# Proto2.net
KiCad netlist of a schematic drawn in EAGLE
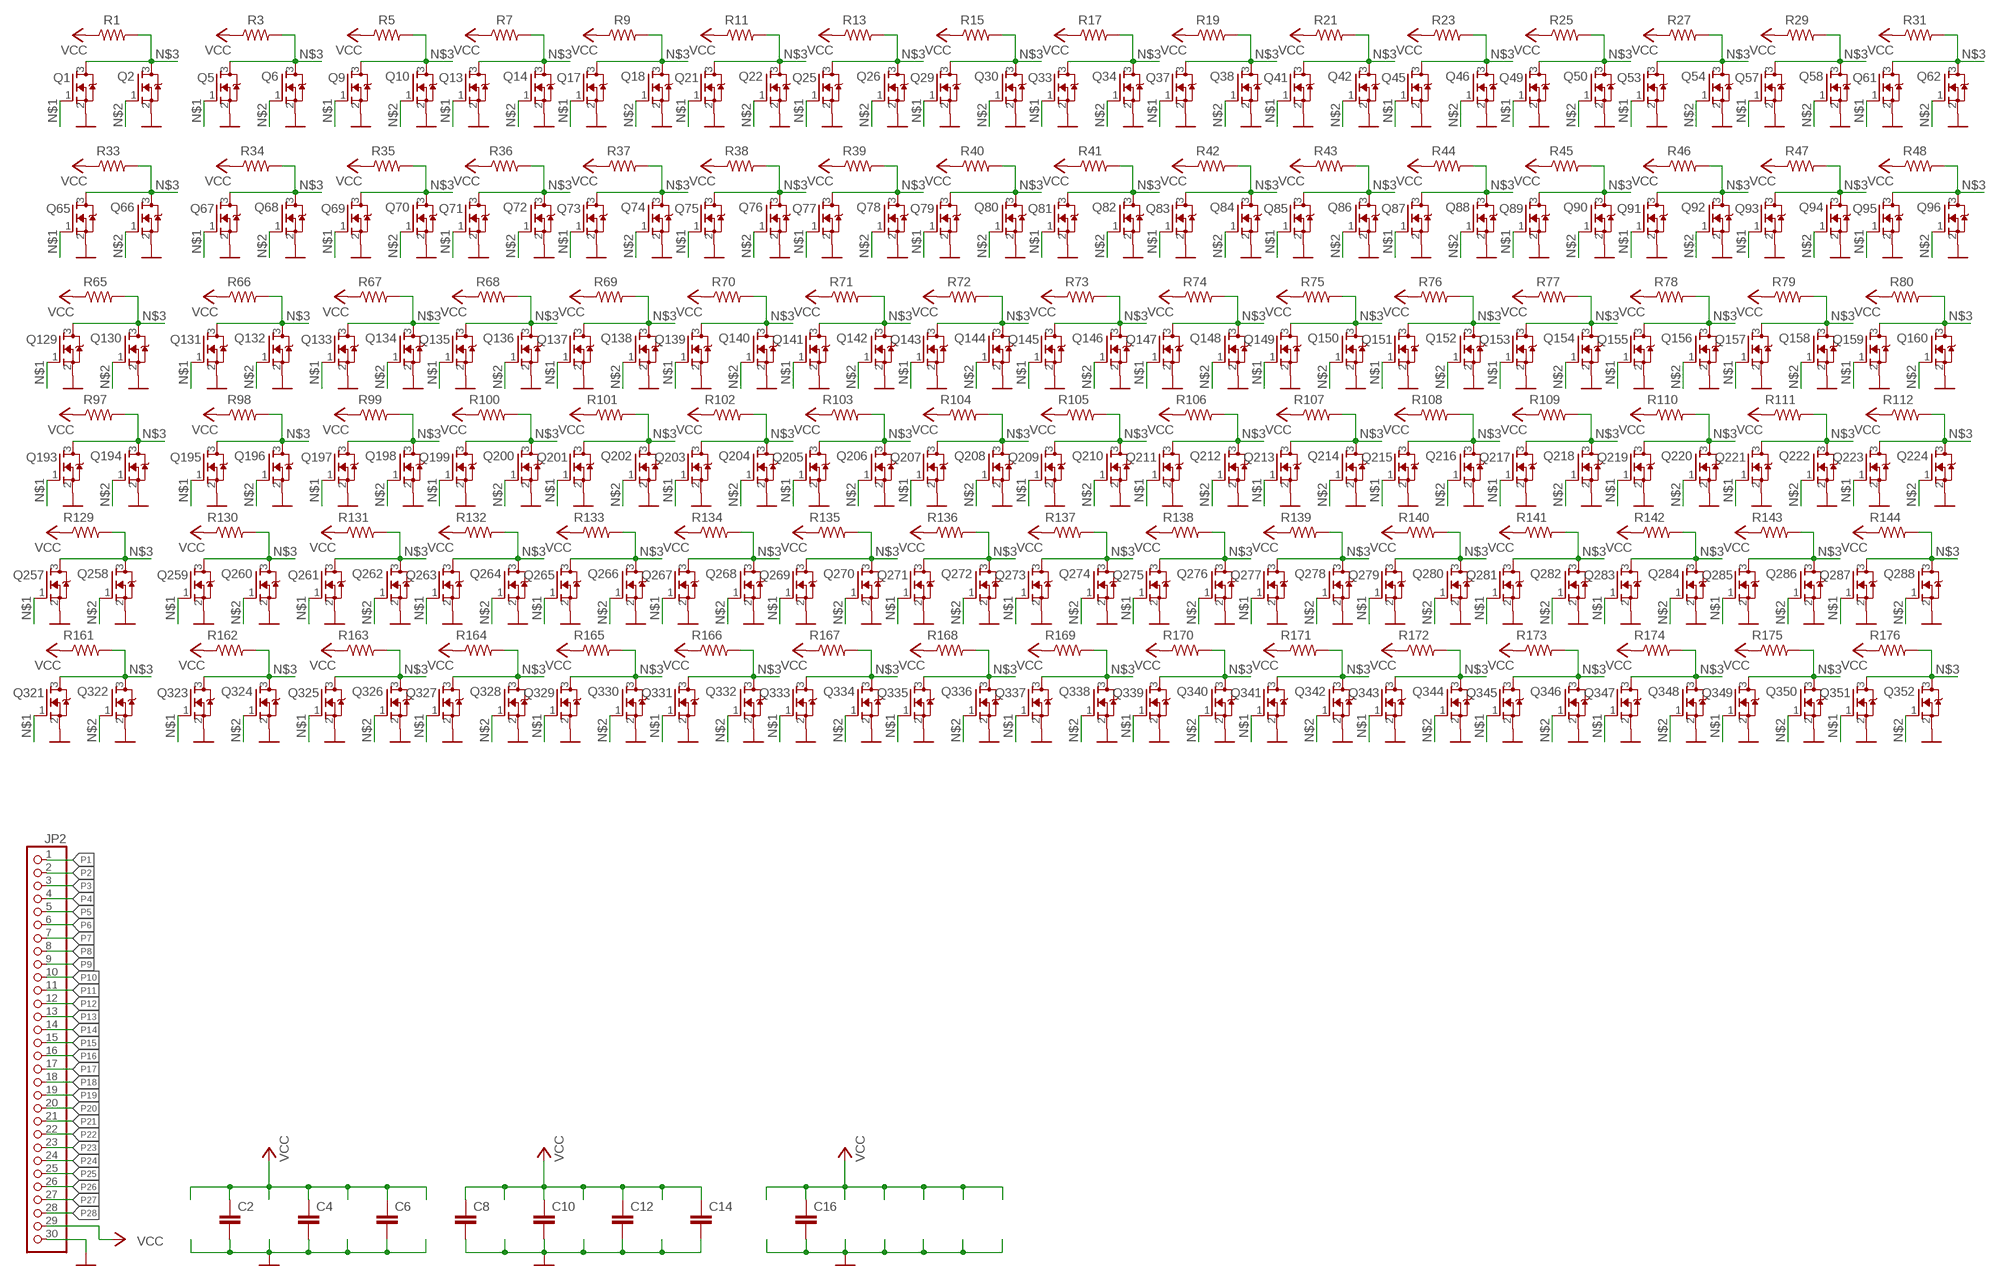
[diagram p0: schematic, sheet 1]

(export (version "E")
  (design (tool "Eeschema 10.0.6"))
  (components
    (comp (ref "C2")
      (value "C-EUC0805K")
      (footprint "eagle-import:C0805K")
      (libsource (lib "eagle-import") (part "C-EUC0805K"))
    )
    (comp (ref "C4")
      (value "C-EUC0805K")
      (footprint "eagle-import:C0805K")
      (libsource (lib "eagle-import") (part "C-EUC0805K"))
    )
    (comp (ref "C6")
      (value "C-EUC0805K")
      (footprint "eagle-import:C0805K")
      (libsource (lib "eagle-import") (part "C-EUC0805K"))
    )
    (comp (ref "C8")
      (value "C-EUC0805K")
      (footprint "eagle-import:C0805K")
      (libsource (lib "eagle-import") (part "C-EUC0805K"))
    )
    (comp (ref "C10")
      (value "C-EUC0805K")
      (footprint "eagle-import:C0805K")
      (libsource (lib "eagle-import") (part "C-EUC0805K"))
    )
    (comp (ref "C12")
      (value "C-EUC0805K")
      (footprint "eagle-import:C0805K")
      (libsource (lib "eagle-import") (part "C-EUC0805K"))
    )
    (comp (ref "C14")
      (value "C-EUC0805K")
      (footprint "eagle-import:C0805K")
      (libsource (lib "eagle-import") (part "C-EUC0805K"))
    )
    (comp (ref "C16")
      (value "C-EUC0805K")
      (footprint "eagle-import:C0805K")
      (libsource (lib "eagle-import") (part "C-EUC0805K"))
    )
    (comp (ref "JP2")
      (value "PINHD-1X30")
      (footprint "eagle-import:1X30")
      (libsource (lib "eagle-import") (part "PINHD-1X30"))
    )
    (comp (ref "Q1")
      (value "310mA/60V/1.6Ω")
      (footprint "eagle-import:SOT23")
      (libsource (lib "eagle-import") (part "NMOSREFLOW"))
    )
    (comp (ref "Q2")
      (value "310mA/60V/1.6Ω")
      (footprint "eagle-import:SOT23")
      (libsource (lib "eagle-import") (part "NMOSREFLOW"))
    )
    (comp (ref "Q5")
      (value "310mA/60V/1.6Ω")
      (footprint "eagle-import:SOT23")
      (libsource (lib "eagle-import") (part "NMOSREFLOW"))
    )
    (comp (ref "Q6")
      (value "310mA/60V/1.6Ω")
      (footprint "eagle-import:SOT23")
      (libsource (lib "eagle-import") (part "NMOSREFLOW"))
    )
    (comp (ref "Q9")
      (value "310mA/60V/1.6Ω")
      (footprint "eagle-import:SOT23")
      (libsource (lib "eagle-import") (part "NMOSREFLOW"))
    )
    (comp (ref "Q10")
      (value "310mA/60V/1.6Ω")
      (footprint "eagle-import:SOT23")
      (libsource (lib "eagle-import") (part "NMOSREFLOW"))
    )
    (comp (ref "Q13")
      (value "310mA/60V/1.6Ω")
      (footprint "eagle-import:SOT23")
      (libsource (lib "eagle-import") (part "NMOSREFLOW"))
    )
    (comp (ref "Q14")
      (value "310mA/60V/1.6Ω")
      (footprint "eagle-import:SOT23")
      (libsource (lib "eagle-import") (part "NMOSREFLOW"))
    )
    (comp (ref "Q17")
      (value "310mA/60V/1.6Ω")
      (footprint "eagle-import:SOT23")
      (libsource (lib "eagle-import") (part "NMOSREFLOW"))
    )
    (comp (ref "Q18")
      (value "310mA/60V/1.6Ω")
      (footprint "eagle-import:SOT23")
      (libsource (lib "eagle-import") (part "NMOSREFLOW"))
    )
    (comp (ref "Q21")
      (value "310mA/60V/1.6Ω")
      (footprint "eagle-import:SOT23")
      (libsource (lib "eagle-import") (part "NMOSREFLOW"))
    )
    (comp (ref "Q22")
      (value "310mA/60V/1.6Ω")
      (footprint "eagle-import:SOT23")
      (libsource (lib "eagle-import") (part "NMOSREFLOW"))
    )
    (comp (ref "Q25")
      (value "310mA/60V/1.6Ω")
      (footprint "eagle-import:SOT23")
      (libsource (lib "eagle-import") (part "NMOSREFLOW"))
    )
    (comp (ref "Q26")
      (value "310mA/60V/1.6Ω")
      (footprint "eagle-import:SOT23")
      (libsource (lib "eagle-import") (part "NMOSREFLOW"))
    )
    (comp (ref "Q29")
      (value "310mA/60V/1.6Ω")
      (footprint "eagle-import:SOT23")
      (libsource (lib "eagle-import") (part "NMOSREFLOW"))
    )
    (comp (ref "Q30")
      (value "310mA/60V/1.6Ω")
      (footprint "eagle-import:SOT23")
      (libsource (lib "eagle-import") (part "NMOSREFLOW"))
    )
    (comp (ref "Q33")
      (value "310mA/60V/1.6Ω")
      (footprint "eagle-import:SOT23")
      (libsource (lib "eagle-import") (part "NMOSREFLOW"))
    )
    (comp (ref "Q34")
      (value "310mA/60V/1.6Ω")
      (footprint "eagle-import:SOT23")
      (libsource (lib "eagle-import") (part "NMOSREFLOW"))
    )
    (comp (ref "Q37")
      (value "310mA/60V/1.6Ω")
      (footprint "eagle-import:SOT23")
      (libsource (lib "eagle-import") (part "NMOSREFLOW"))
    )
    (comp (ref "Q38")
      (value "310mA/60V/1.6Ω")
      (footprint "eagle-import:SOT23")
      (libsource (lib "eagle-import") (part "NMOSREFLOW"))
    )
    (comp (ref "Q41")
      (value "310mA/60V/1.6Ω")
      (footprint "eagle-import:SOT23")
      (libsource (lib "eagle-import") (part "NMOSREFLOW"))
    )
    (comp (ref "Q42")
      (value "310mA/60V/1.6Ω")
      (footprint "eagle-import:SOT23")
      (libsource (lib "eagle-import") (part "NMOSREFLOW"))
    )
    (comp (ref "Q45")
      (value "310mA/60V/1.6Ω")
      (footprint "eagle-import:SOT23")
      (libsource (lib "eagle-import") (part "NMOSREFLOW"))
    )
    (comp (ref "Q46")
      (value "310mA/60V/1.6Ω")
      (footprint "eagle-import:SOT23")
      (libsource (lib "eagle-import") (part "NMOSREFLOW"))
    )
    (comp (ref "Q49")
      (value "310mA/60V/1.6Ω")
      (footprint "eagle-import:SOT23")
      (libsource (lib "eagle-import") (part "NMOSREFLOW"))
    )
    (comp (ref "Q50")
      (value "310mA/60V/1.6Ω")
      (footprint "eagle-import:SOT23")
      (libsource (lib "eagle-import") (part "NMOSREFLOW"))
    )
    (comp (ref "Q53")
      (value "310mA/60V/1.6Ω")
      (footprint "eagle-import:SOT23")
      (libsource (lib "eagle-import") (part "NMOSREFLOW"))
    )
    (comp (ref "Q54")
      (value "310mA/60V/1.6Ω")
      (footprint "eagle-import:SOT23")
      (libsource (lib "eagle-import") (part "NMOSREFLOW"))
    )
    (comp (ref "Q57")
      (value "310mA/60V/1.6Ω")
      (footprint "eagle-import:SOT23")
      (libsource (lib "eagle-import") (part "NMOSREFLOW"))
    )
    (comp (ref "Q58")
      (value "310mA/60V/1.6Ω")
      (footprint "eagle-import:SOT23")
      (libsource (lib "eagle-import") (part "NMOSREFLOW"))
    )
    (comp (ref "Q61")
      (value "310mA/60V/1.6Ω")
      (footprint "eagle-import:SOT23")
      (libsource (lib "eagle-import") (part "NMOSREFLOW"))
    )
    (comp (ref "Q62")
      (value "310mA/60V/1.6Ω")
      (footprint "eagle-import:SOT23")
      (libsource (lib "eagle-import") (part "NMOSREFLOW"))
    )
    (comp (ref "Q65")
      (value "310mA/60V/1.6Ω")
      (footprint "eagle-import:SOT23")
      (libsource (lib "eagle-import") (part "NMOSREFLOW"))
    )
    (comp (ref "Q66")
      (value "310mA/60V/1.6Ω")
      (footprint "eagle-import:SOT23")
      (libsource (lib "eagle-import") (part "NMOSREFLOW"))
    )
    (comp (ref "Q67")
      (value "310mA/60V/1.6Ω")
      (footprint "eagle-import:SOT23")
      (libsource (lib "eagle-import") (part "NMOSREFLOW"))
    )
    (comp (ref "Q68")
      (value "310mA/60V/1.6Ω")
      (footprint "eagle-import:SOT23")
      (libsource (lib "eagle-import") (part "NMOSREFLOW"))
    )
    (comp (ref "Q69")
      (value "310mA/60V/1.6Ω")
      (footprint "eagle-import:SOT23")
      (libsource (lib "eagle-import") (part "NMOSREFLOW"))
    )
    (comp (ref "Q70")
      (value "310mA/60V/1.6Ω")
      (footprint "eagle-import:SOT23")
      (libsource (lib "eagle-import") (part "NMOSREFLOW"))
    )
    (comp (ref "Q71")
      (value "310mA/60V/1.6Ω")
      (footprint "eagle-import:SOT23")
      (libsource (lib "eagle-import") (part "NMOSREFLOW"))
    )
    (comp (ref "Q72")
      (value "310mA/60V/1.6Ω")
      (footprint "eagle-import:SOT23")
      (libsource (lib "eagle-import") (part "NMOSREFLOW"))
    )
    (comp (ref "Q73")
      (value "310mA/60V/1.6Ω")
      (footprint "eagle-import:SOT23")
      (libsource (lib "eagle-import") (part "NMOSREFLOW"))
    )
    (comp (ref "Q74")
      (value "310mA/60V/1.6Ω")
      (footprint "eagle-import:SOT23")
      (libsource (lib "eagle-import") (part "NMOSREFLOW"))
    )
    (comp (ref "Q75")
      (value "310mA/60V/1.6Ω")
      (footprint "eagle-import:SOT23")
      (libsource (lib "eagle-import") (part "NMOSREFLOW"))
    )
    (comp (ref "Q76")
      (value "310mA/60V/1.6Ω")
      (footprint "eagle-import:SOT23")
      (libsource (lib "eagle-import") (part "NMOSREFLOW"))
    )
    (comp (ref "Q77")
      (value "310mA/60V/1.6Ω")
      (footprint "eagle-import:SOT23")
      (libsource (lib "eagle-import") (part "NMOSREFLOW"))
    )
    (comp (ref "Q78")
      (value "310mA/60V/1.6Ω")
      (footprint "eagle-import:SOT23")
      (libsource (lib "eagle-import") (part "NMOSREFLOW"))
    )
    (comp (ref "Q79")
      (value "310mA/60V/1.6Ω")
      (footprint "eagle-import:SOT23")
      (libsource (lib "eagle-import") (part "NMOSREFLOW"))
    )
    (comp (ref "Q80")
      (value "310mA/60V/1.6Ω")
      (footprint "eagle-import:SOT23")
      (libsource (lib "eagle-import") (part "NMOSREFLOW"))
    )
    (comp (ref "Q81")
      (value "310mA/60V/1.6Ω")
      (footprint "eagle-import:SOT23")
      (libsource (lib "eagle-import") (part "NMOSREFLOW"))
    )
    (comp (ref "Q82")
      (value "310mA/60V/1.6Ω")
      (footprint "eagle-import:SOT23")
      (libsource (lib "eagle-import") (part "NMOSREFLOW"))
    )
    (comp (ref "Q83")
      (value "310mA/60V/1.6Ω")
      (footprint "eagle-import:SOT23")
      (libsource (lib "eagle-import") (part "NMOSREFLOW"))
    )
    (comp (ref "Q84")
      (value "310mA/60V/1.6Ω")
      (footprint "eagle-import:SOT23")
      (libsource (lib "eagle-import") (part "NMOSREFLOW"))
    )
    (comp (ref "Q85")
      (value "310mA/60V/1.6Ω")
      (footprint "eagle-import:SOT23")
      (libsource (lib "eagle-import") (part "NMOSREFLOW"))
    )
    (comp (ref "Q86")
      (value "310mA/60V/1.6Ω")
      (footprint "eagle-import:SOT23")
      (libsource (lib "eagle-import") (part "NMOSREFLOW"))
    )
    (comp (ref "Q87")
      (value "310mA/60V/1.6Ω")
      (footprint "eagle-import:SOT23")
      (libsource (lib "eagle-import") (part "NMOSREFLOW"))
    )
    (comp (ref "Q88")
      (value "310mA/60V/1.6Ω")
      (footprint "eagle-import:SOT23")
      (libsource (lib "eagle-import") (part "NMOSREFLOW"))
    )
    (comp (ref "Q89")
      (value "310mA/60V/1.6Ω")
      (footprint "eagle-import:SOT23")
      (libsource (lib "eagle-import") (part "NMOSREFLOW"))
    )
    (comp (ref "Q90")
      (value "310mA/60V/1.6Ω")
      (footprint "eagle-import:SOT23")
      (libsource (lib "eagle-import") (part "NMOSREFLOW"))
    )
    (comp (ref "Q91")
      (value "310mA/60V/1.6Ω")
      (footprint "eagle-import:SOT23")
      (libsource (lib "eagle-import") (part "NMOSREFLOW"))
    )
    (comp (ref "Q92")
      (value "310mA/60V/1.6Ω")
      (footprint "eagle-import:SOT23")
      (libsource (lib "eagle-import") (part "NMOSREFLOW"))
    )
    (comp (ref "Q93")
      (value "310mA/60V/1.6Ω")
      (footprint "eagle-import:SOT23")
      (libsource (lib "eagle-import") (part "NMOSREFLOW"))
    )
    (comp (ref "Q94")
      (value "310mA/60V/1.6Ω")
      (footprint "eagle-import:SOT23")
      (libsource (lib "eagle-import") (part "NMOSREFLOW"))
    )
    (comp (ref "Q95")
      (value "310mA/60V/1.6Ω")
      (footprint "eagle-import:SOT23")
      (libsource (lib "eagle-import") (part "NMOSREFLOW"))
    )
    (comp (ref "Q96")
      (value "310mA/60V/1.6Ω")
      (footprint "eagle-import:SOT23")
      (libsource (lib "eagle-import") (part "NMOSREFLOW"))
    )
    (comp (ref "Q129")
      (value "310mA/60V/1.6Ω")
      (footprint "eagle-import:SOT23")
      (libsource (lib "eagle-import") (part "NMOSREFLOW"))
    )
    (comp (ref "Q130")
      (value "310mA/60V/1.6Ω")
      (footprint "eagle-import:SOT23")
      (libsource (lib "eagle-import") (part "NMOSREFLOW"))
    )
    (comp (ref "Q131")
      (value "310mA/60V/1.6Ω")
      (footprint "eagle-import:SOT23")
      (libsource (lib "eagle-import") (part "NMOSREFLOW"))
    )
    (comp (ref "Q132")
      (value "310mA/60V/1.6Ω")
      (footprint "eagle-import:SOT23")
      (libsource (lib "eagle-import") (part "NMOSREFLOW"))
    )
    (comp (ref "Q133")
      (value "310mA/60V/1.6Ω")
      (footprint "eagle-import:SOT23")
      (libsource (lib "eagle-import") (part "NMOSREFLOW"))
    )
    (comp (ref "Q134")
      (value "310mA/60V/1.6Ω")
      (footprint "eagle-import:SOT23")
      (libsource (lib "eagle-import") (part "NMOSREFLOW"))
    )
    (comp (ref "Q135")
      (value "310mA/60V/1.6Ω")
      (footprint "eagle-import:SOT23")
      (libsource (lib "eagle-import") (part "NMOSREFLOW"))
    )
    (comp (ref "Q136")
      (value "310mA/60V/1.6Ω")
      (footprint "eagle-import:SOT23")
      (libsource (lib "eagle-import") (part "NMOSREFLOW"))
    )
    (comp (ref "Q137")
      (value "310mA/60V/1.6Ω")
      (footprint "eagle-import:SOT23")
      (libsource (lib "eagle-import") (part "NMOSREFLOW"))
    )
    (comp (ref "Q138")
      (value "310mA/60V/1.6Ω")
      (footprint "eagle-import:SOT23")
      (libsource (lib "eagle-import") (part "NMOSREFLOW"))
    )
    (comp (ref "Q139")
      (value "310mA/60V/1.6Ω")
      (footprint "eagle-import:SOT23")
      (libsource (lib "eagle-import") (part "NMOSREFLOW"))
    )
    (comp (ref "Q140")
      (value "310mA/60V/1.6Ω")
      (footprint "eagle-import:SOT23")
      (libsource (lib "eagle-import") (part "NMOSREFLOW"))
    )
    (comp (ref "Q141")
      (value "310mA/60V/1.6Ω")
      (footprint "eagle-import:SOT23")
      (libsource (lib "eagle-import") (part "NMOSREFLOW"))
    )
    (comp (ref "Q142")
      (value "310mA/60V/1.6Ω")
      (footprint "eagle-import:SOT23")
      (libsource (lib "eagle-import") (part "NMOSREFLOW"))
    )
    (comp (ref "Q143")
      (value "310mA/60V/1.6Ω")
      (footprint "eagle-import:SOT23")
      (libsource (lib "eagle-import") (part "NMOSREFLOW"))
    )
    (comp (ref "Q144")
      (value "310mA/60V/1.6Ω")
      (footprint "eagle-import:SOT23")
      (libsource (lib "eagle-import") (part "NMOSREFLOW"))
    )
    (comp (ref "Q145")
      (value "310mA/60V/1.6Ω")
      (footprint "eagle-import:SOT23")
      (libsource (lib "eagle-import") (part "NMOSREFLOW"))
    )
    (comp (ref "Q146")
      (value "310mA/60V/1.6Ω")
      (footprint "eagle-import:SOT23")
      (libsource (lib "eagle-import") (part "NMOSREFLOW"))
    )
    (comp (ref "Q147")
      (value "310mA/60V/1.6Ω")
      (footprint "eagle-import:SOT23")
      (libsource (lib "eagle-import") (part "NMOSREFLOW"))
    )
    (comp (ref "Q148")
      (value "310mA/60V/1.6Ω")
      (footprint "eagle-import:SOT23")
      (libsource (lib "eagle-import") (part "NMOSREFLOW"))
    )
    (comp (ref "Q149")
      (value "310mA/60V/1.6Ω")
      (footprint "eagle-import:SOT23")
      (libsource (lib "eagle-import") (part "NMOSREFLOW"))
    )
    (comp (ref "Q150")
      (value "310mA/60V/1.6Ω")
      (footprint "eagle-import:SOT23")
      (libsource (lib "eagle-import") (part "NMOSREFLOW"))
    )
    (comp (ref "Q151")
      (value "310mA/60V/1.6Ω")
      (footprint "eagle-import:SOT23")
      (libsource (lib "eagle-import") (part "NMOSREFLOW"))
    )
    (comp (ref "Q152")
      (value "310mA/60V/1.6Ω")
      (footprint "eagle-import:SOT23")
      (libsource (lib "eagle-import") (part "NMOSREFLOW"))
    )
    (comp (ref "Q153")
      (value "310mA/60V/1.6Ω")
      (footprint "eagle-import:SOT23")
      (libsource (lib "eagle-import") (part "NMOSREFLOW"))
    )
    (comp (ref "Q154")
      (value "310mA/60V/1.6Ω")
      (footprint "eagle-import:SOT23")
      (libsource (lib "eagle-import") (part "NMOSREFLOW"))
    )
    (comp (ref "Q155")
      (value "310mA/60V/1.6Ω")
      (footprint "eagle-import:SOT23")
      (libsource (lib "eagle-import") (part "NMOSREFLOW"))
    )
    (comp (ref "Q156")
      (value "310mA/60V/1.6Ω")
      (footprint "eagle-import:SOT23")
      (libsource (lib "eagle-import") (part "NMOSREFLOW"))
    )
    (comp (ref "Q157")
      (value "310mA/60V/1.6Ω")
      (footprint "eagle-import:SOT23")
      (libsource (lib "eagle-import") (part "NMOSREFLOW"))
    )
    (comp (ref "Q158")
      (value "310mA/60V/1.6Ω")
      (footprint "eagle-import:SOT23")
      (libsource (lib "eagle-import") (part "NMOSREFLOW"))
    )
    (comp (ref "Q159")
      (value "310mA/60V/1.6Ω")
      (footprint "eagle-import:SOT23")
      (libsource (lib "eagle-import") (part "NMOSREFLOW"))
    )
    (comp (ref "Q160")
      (value "310mA/60V/1.6Ω")
      (footprint "eagle-import:SOT23")
      (libsource (lib "eagle-import") (part "NMOSREFLOW"))
    )
    (comp (ref "Q193")
      (value "310mA/60V/1.6Ω")
      (footprint "eagle-import:SOT23")
      (libsource (lib "eagle-import") (part "NMOSREFLOW"))
    )
    (comp (ref "Q194")
      (value "310mA/60V/1.6Ω")
      (footprint "eagle-import:SOT23")
      (libsource (lib "eagle-import") (part "NMOSREFLOW"))
    )
    (comp (ref "Q195")
      (value "310mA/60V/1.6Ω")
      (footprint "eagle-import:SOT23")
      (libsource (lib "eagle-import") (part "NMOSREFLOW"))
    )
    (comp (ref "Q196")
      (value "310mA/60V/1.6Ω")
      (footprint "eagle-import:SOT23")
      (libsource (lib "eagle-import") (part "NMOSREFLOW"))
    )
    (comp (ref "Q197")
      (value "310mA/60V/1.6Ω")
      (footprint "eagle-import:SOT23")
      (libsource (lib "eagle-import") (part "NMOSREFLOW"))
    )
    (comp (ref "Q198")
      (value "310mA/60V/1.6Ω")
      (footprint "eagle-import:SOT23")
      (libsource (lib "eagle-import") (part "NMOSREFLOW"))
    )
    (comp (ref "Q199")
      (value "310mA/60V/1.6Ω")
      (footprint "eagle-import:SOT23")
      (libsource (lib "eagle-import") (part "NMOSREFLOW"))
    )
    (comp (ref "Q200")
      (value "310mA/60V/1.6Ω")
      (footprint "eagle-import:SOT23")
      (libsource (lib "eagle-import") (part "NMOSREFLOW"))
    )
    (comp (ref "Q201")
      (value "310mA/60V/1.6Ω")
      (footprint "eagle-import:SOT23")
      (libsource (lib "eagle-import") (part "NMOSREFLOW"))
    )
    (comp (ref "Q202")
      (value "310mA/60V/1.6Ω")
      (footprint "eagle-import:SOT23")
      (libsource (lib "eagle-import") (part "NMOSREFLOW"))
    )
    (comp (ref "Q203")
      (value "310mA/60V/1.6Ω")
      (footprint "eagle-import:SOT23")
      (libsource (lib "eagle-import") (part "NMOSREFLOW"))
    )
    (comp (ref "Q204")
      (value "310mA/60V/1.6Ω")
      (footprint "eagle-import:SOT23")
      (libsource (lib "eagle-import") (part "NMOSREFLOW"))
    )
    (comp (ref "Q205")
      (value "310mA/60V/1.6Ω")
      (footprint "eagle-import:SOT23")
      (libsource (lib "eagle-import") (part "NMOSREFLOW"))
    )
    (comp (ref "Q206")
      (value "310mA/60V/1.6Ω")
      (footprint "eagle-import:SOT23")
      (libsource (lib "eagle-import") (part "NMOSREFLOW"))
    )
    (comp (ref "Q207")
      (value "310mA/60V/1.6Ω")
      (footprint "eagle-import:SOT23")
      (libsource (lib "eagle-import") (part "NMOSREFLOW"))
    )
    (comp (ref "Q208")
      (value "310mA/60V/1.6Ω")
      (footprint "eagle-import:SOT23")
      (libsource (lib "eagle-import") (part "NMOSREFLOW"))
    )
    (comp (ref "Q209")
      (value "310mA/60V/1.6Ω")
      (footprint "eagle-import:SOT23")
      (libsource (lib "eagle-import") (part "NMOSREFLOW"))
    )
    (comp (ref "Q210")
      (value "310mA/60V/1.6Ω")
      (footprint "eagle-import:SOT23")
      (libsource (lib "eagle-import") (part "NMOSREFLOW"))
    )
    (comp (ref "Q211")
      (value "310mA/60V/1.6Ω")
      (footprint "eagle-import:SOT23")
      (libsource (lib "eagle-import") (part "NMOSREFLOW"))
    )
    (comp (ref "Q212")
      (value "310mA/60V/1.6Ω")
      (footprint "eagle-import:SOT23")
      (libsource (lib "eagle-import") (part "NMOSREFLOW"))
    )
    (comp (ref "Q213")
      (value "310mA/60V/1.6Ω")
      (footprint "eagle-import:SOT23")
      (libsource (lib "eagle-import") (part "NMOSREFLOW"))
    )
    (comp (ref "Q214")
      (value "310mA/60V/1.6Ω")
      (footprint "eagle-import:SOT23")
      (libsource (lib "eagle-import") (part "NMOSREFLOW"))
    )
    (comp (ref "Q215")
      (value "310mA/60V/1.6Ω")
      (footprint "eagle-import:SOT23")
      (libsource (lib "eagle-import") (part "NMOSREFLOW"))
    )
    (comp (ref "Q216")
      (value "310mA/60V/1.6Ω")
      (footprint "eagle-import:SOT23")
      (libsource (lib "eagle-import") (part "NMOSREFLOW"))
    )
    (comp (ref "Q217")
      (value "310mA/60V/1.6Ω")
      (footprint "eagle-import:SOT23")
      (libsource (lib "eagle-import") (part "NMOSREFLOW"))
    )
    (comp (ref "Q218")
      (value "310mA/60V/1.6Ω")
      (footprint "eagle-import:SOT23")
      (libsource (lib "eagle-import") (part "NMOSREFLOW"))
    )
    (comp (ref "Q219")
      (value "310mA/60V/1.6Ω")
      (footprint "eagle-import:SOT23")
      (libsource (lib "eagle-import") (part "NMOSREFLOW"))
    )
    (comp (ref "Q220")
      (value "310mA/60V/1.6Ω")
      (footprint "eagle-import:SOT23")
      (libsource (lib "eagle-import") (part "NMOSREFLOW"))
    )
    (comp (ref "Q221")
      (value "310mA/60V/1.6Ω")
      (footprint "eagle-import:SOT23")
      (libsource (lib "eagle-import") (part "NMOSREFLOW"))
    )
    (comp (ref "Q222")
      (value "310mA/60V/1.6Ω")
      (footprint "eagle-import:SOT23")
      (libsource (lib "eagle-import") (part "NMOSREFLOW"))
    )
    (comp (ref "Q223")
      (value "310mA/60V/1.6Ω")
      (footprint "eagle-import:SOT23")
      (libsource (lib "eagle-import") (part "NMOSREFLOW"))
    )
    (comp (ref "Q224")
      (value "310mA/60V/1.6Ω")
      (footprint "eagle-import:SOT23")
      (libsource (lib "eagle-import") (part "NMOSREFLOW"))
    )
    (comp (ref "Q257")
      (value "310mA/60V/1.6Ω")
      (footprint "eagle-import:SOT23")
      (libsource (lib "eagle-import") (part "NMOSREFLOW"))
    )
    (comp (ref "Q258")
      (value "310mA/60V/1.6Ω")
      (footprint "eagle-import:SOT23")
      (libsource (lib "eagle-import") (part "NMOSREFLOW"))
    )
    (comp (ref "Q259")
      (value "310mA/60V/1.6Ω")
      (footprint "eagle-import:SOT23")
      (libsource (lib "eagle-import") (part "NMOSREFLOW"))
    )
    (comp (ref "Q260")
      (value "310mA/60V/1.6Ω")
      (footprint "eagle-import:SOT23")
      (libsource (lib "eagle-import") (part "NMOSREFLOW"))
    )
    (comp (ref "Q261")
      (value "310mA/60V/1.6Ω")
      (footprint "eagle-import:SOT23")
      (libsource (lib "eagle-import") (part "NMOSREFLOW"))
    )
    (comp (ref "Q262")
      (value "310mA/60V/1.6Ω")
      (footprint "eagle-import:SOT23")
      (libsource (lib "eagle-import") (part "NMOSREFLOW"))
    )
    (comp (ref "Q263")
      (value "310mA/60V/1.6Ω")
      (footprint "eagle-import:SOT23")
      (libsource (lib "eagle-import") (part "NMOSREFLOW"))
    )
    (comp (ref "Q264")
      (value "310mA/60V/1.6Ω")
      (footprint "eagle-import:SOT23")
      (libsource (lib "eagle-import") (part "NMOSREFLOW"))
    )
    (comp (ref "Q265")
      (value "310mA/60V/1.6Ω")
      (footprint "eagle-import:SOT23")
      (libsource (lib "eagle-import") (part "NMOSREFLOW"))
    )
    (comp (ref "Q266")
      (value "310mA/60V/1.6Ω")
      (footprint "eagle-import:SOT23")
      (libsource (lib "eagle-import") (part "NMOSREFLOW"))
    )
    (comp (ref "Q267")
      (value "310mA/60V/1.6Ω")
      (footprint "eagle-import:SOT23")
      (libsource (lib "eagle-import") (part "NMOSREFLOW"))
    )
    (comp (ref "Q268")
      (value "310mA/60V/1.6Ω")
      (footprint "eagle-import:SOT23")
      (libsource (lib "eagle-import") (part "NMOSREFLOW"))
    )
    (comp (ref "Q269")
      (value "310mA/60V/1.6Ω")
      (footprint "eagle-import:SOT23")
      (libsource (lib "eagle-import") (part "NMOSREFLOW"))
    )
    (comp (ref "Q270")
      (value "310mA/60V/1.6Ω")
      (footprint "eagle-import:SOT23")
      (libsource (lib "eagle-import") (part "NMOSREFLOW"))
    )
    (comp (ref "Q271")
      (value "310mA/60V/1.6Ω")
      (footprint "eagle-import:SOT23")
      (libsource (lib "eagle-import") (part "NMOSREFLOW"))
    )
    (comp (ref "Q272")
      (value "310mA/60V/1.6Ω")
      (footprint "eagle-import:SOT23")
      (libsource (lib "eagle-import") (part "NMOSREFLOW"))
    )
    (comp (ref "Q273")
      (value "310mA/60V/1.6Ω")
      (footprint "eagle-import:SOT23")
      (libsource (lib "eagle-import") (part "NMOSREFLOW"))
    )
    (comp (ref "Q274")
      (value "310mA/60V/1.6Ω")
      (footprint "eagle-import:SOT23")
      (libsource (lib "eagle-import") (part "NMOSREFLOW"))
    )
    (comp (ref "Q275")
      (value "310mA/60V/1.6Ω")
      (footprint "eagle-import:SOT23")
      (libsource (lib "eagle-import") (part "NMOSREFLOW"))
    )
    (comp (ref "Q276")
      (value "310mA/60V/1.6Ω")
      (footprint "eagle-import:SOT23")
      (libsource (lib "eagle-import") (part "NMOSREFLOW"))
    )
    (comp (ref "Q277")
      (value "310mA/60V/1.6Ω")
      (footprint "eagle-import:SOT23")
      (libsource (lib "eagle-import") (part "NMOSREFLOW"))
    )
    (comp (ref "Q278")
      (value "310mA/60V/1.6Ω")
      (footprint "eagle-import:SOT23")
      (libsource (lib "eagle-import") (part "NMOSREFLOW"))
    )
    (comp (ref "Q279")
      (value "310mA/60V/1.6Ω")
      (footprint "eagle-import:SOT23")
      (libsource (lib "eagle-import") (part "NMOSREFLOW"))
    )
    (comp (ref "Q280")
      (value "310mA/60V/1.6Ω")
      (footprint "eagle-import:SOT23")
      (libsource (lib "eagle-import") (part "NMOSREFLOW"))
    )
    (comp (ref "Q281")
      (value "310mA/60V/1.6Ω")
      (footprint "eagle-import:SOT23")
      (libsource (lib "eagle-import") (part "NMOSREFLOW"))
    )
    (comp (ref "Q282")
      (value "310mA/60V/1.6Ω")
      (footprint "eagle-import:SOT23")
      (libsource (lib "eagle-import") (part "NMOSREFLOW"))
    )
    (comp (ref "Q283")
      (value "310mA/60V/1.6Ω")
      (footprint "eagle-import:SOT23")
      (libsource (lib "eagle-import") (part "NMOSREFLOW"))
    )
    (comp (ref "Q284")
      (value "310mA/60V/1.6Ω")
      (footprint "eagle-import:SOT23")
      (libsource (lib "eagle-import") (part "NMOSREFLOW"))
    )
    (comp (ref "Q285")
      (value "310mA/60V/1.6Ω")
      (footprint "eagle-import:SOT23")
      (libsource (lib "eagle-import") (part "NMOSREFLOW"))
    )
    (comp (ref "Q286")
      (value "310mA/60V/1.6Ω")
      (footprint "eagle-import:SOT23")
      (libsource (lib "eagle-import") (part "NMOSREFLOW"))
    )
    (comp (ref "Q287")
      (value "310mA/60V/1.6Ω")
      (footprint "eagle-import:SOT23")
      (libsource (lib "eagle-import") (part "NMOSREFLOW"))
    )
    (comp (ref "Q288")
      (value "310mA/60V/1.6Ω")
      (footprint "eagle-import:SOT23")
      (libsource (lib "eagle-import") (part "NMOSREFLOW"))
    )
    (comp (ref "Q321")
      (value "310mA/60V/1.6Ω")
      (footprint "eagle-import:SOT23")
      (libsource (lib "eagle-import") (part "NMOSREFLOW"))
    )
    (comp (ref "Q322")
      (value "310mA/60V/1.6Ω")
      (footprint "eagle-import:SOT23")
      (libsource (lib "eagle-import") (part "NMOSREFLOW"))
    )
    (comp (ref "Q323")
      (value "310mA/60V/1.6Ω")
      (footprint "eagle-import:SOT23")
      (libsource (lib "eagle-import") (part "NMOSREFLOW"))
    )
    (comp (ref "Q324")
      (value "310mA/60V/1.6Ω")
      (footprint "eagle-import:SOT23")
      (libsource (lib "eagle-import") (part "NMOSREFLOW"))
    )
    (comp (ref "Q325")
      (value "310mA/60V/1.6Ω")
      (footprint "eagle-import:SOT23")
      (libsource (lib "eagle-import") (part "NMOSREFLOW"))
    )
    (comp (ref "Q326")
      (value "310mA/60V/1.6Ω")
      (footprint "eagle-import:SOT23")
      (libsource (lib "eagle-import") (part "NMOSREFLOW"))
    )
    (comp (ref "Q327")
      (value "310mA/60V/1.6Ω")
      (footprint "eagle-import:SOT23")
      (libsource (lib "eagle-import") (part "NMOSREFLOW"))
    )
    (comp (ref "Q328")
      (value "310mA/60V/1.6Ω")
      (footprint "eagle-import:SOT23")
      (libsource (lib "eagle-import") (part "NMOSREFLOW"))
    )
    (comp (ref "Q329")
      (value "310mA/60V/1.6Ω")
      (footprint "eagle-import:SOT23")
      (libsource (lib "eagle-import") (part "NMOSREFLOW"))
    )
    (comp (ref "Q330")
      (value "310mA/60V/1.6Ω")
      (footprint "eagle-import:SOT23")
      (libsource (lib "eagle-import") (part "NMOSREFLOW"))
    )
    (comp (ref "Q331")
      (value "310mA/60V/1.6Ω")
      (footprint "eagle-import:SOT23")
      (libsource (lib "eagle-import") (part "NMOSREFLOW"))
    )
    (comp (ref "Q332")
      (value "310mA/60V/1.6Ω")
      (footprint "eagle-import:SOT23")
      (libsource (lib "eagle-import") (part "NMOSREFLOW"))
    )
    (comp (ref "Q333")
      (value "310mA/60V/1.6Ω")
      (footprint "eagle-import:SOT23")
      (libsource (lib "eagle-import") (part "NMOSREFLOW"))
    )
    (comp (ref "Q334")
      (value "310mA/60V/1.6Ω")
      (footprint "eagle-import:SOT23")
      (libsource (lib "eagle-import") (part "NMOSREFLOW"))
    )
    (comp (ref "Q335")
      (value "310mA/60V/1.6Ω")
      (footprint "eagle-import:SOT23")
      (libsource (lib "eagle-import") (part "NMOSREFLOW"))
    )
    (comp (ref "Q336")
      (value "310mA/60V/1.6Ω")
      (footprint "eagle-import:SOT23")
      (libsource (lib "eagle-import") (part "NMOSREFLOW"))
    )
    (comp (ref "Q337")
      (value "310mA/60V/1.6Ω")
      (footprint "eagle-import:SOT23")
      (libsource (lib "eagle-import") (part "NMOSREFLOW"))
    )
    (comp (ref "Q338")
      (value "310mA/60V/1.6Ω")
      (footprint "eagle-import:SOT23")
      (libsource (lib "eagle-import") (part "NMOSREFLOW"))
    )
    (comp (ref "Q339")
      (value "310mA/60V/1.6Ω")
      (footprint "eagle-import:SOT23")
      (libsource (lib "eagle-import") (part "NMOSREFLOW"))
    )
    (comp (ref "Q340")
      (value "310mA/60V/1.6Ω")
      (footprint "eagle-import:SOT23")
      (libsource (lib "eagle-import") (part "NMOSREFLOW"))
    )
    (comp (ref "Q341")
      (value "310mA/60V/1.6Ω")
      (footprint "eagle-import:SOT23")
      (libsource (lib "eagle-import") (part "NMOSREFLOW"))
    )
    (comp (ref "Q342")
      (value "310mA/60V/1.6Ω")
      (footprint "eagle-import:SOT23")
      (libsource (lib "eagle-import") (part "NMOSREFLOW"))
    )
    (comp (ref "Q343")
      (value "310mA/60V/1.6Ω")
      (footprint "eagle-import:SOT23")
      (libsource (lib "eagle-import") (part "NMOSREFLOW"))
    )
    (comp (ref "Q344")
      (value "310mA/60V/1.6Ω")
      (footprint "eagle-import:SOT23")
      (libsource (lib "eagle-import") (part "NMOSREFLOW"))
    )
    (comp (ref "Q345")
      (value "310mA/60V/1.6Ω")
      (footprint "eagle-import:SOT23")
      (libsource (lib "eagle-import") (part "NMOSREFLOW"))
    )
    (comp (ref "Q346")
      (value "310mA/60V/1.6Ω")
      (footprint "eagle-import:SOT23")
      (libsource (lib "eagle-import") (part "NMOSREFLOW"))
    )
    (comp (ref "Q347")
      (value "310mA/60V/1.6Ω")
      (footprint "eagle-import:SOT23")
      (libsource (lib "eagle-import") (part "NMOSREFLOW"))
    )
    (comp (ref "Q348")
      (value "310mA/60V/1.6Ω")
      (footprint "eagle-import:SOT23")
      (libsource (lib "eagle-import") (part "NMOSREFLOW"))
    )
    (comp (ref "Q349")
      (value "310mA/60V/1.6Ω")
      (footprint "eagle-import:SOT23")
      (libsource (lib "eagle-import") (part "NMOSREFLOW"))
    )
    (comp (ref "Q350")
      (value "310mA/60V/1.6Ω")
      (footprint "eagle-import:SOT23")
      (libsource (lib "eagle-import") (part "NMOSREFLOW"))
    )
    (comp (ref "Q351")
      (value "310mA/60V/1.6Ω")
      (footprint "eagle-import:SOT23")
      (libsource (lib "eagle-import") (part "NMOSREFLOW"))
    )
    (comp (ref "Q352")
      (value "310mA/60V/1.6Ω")
      (footprint "eagle-import:SOT23")
      (libsource (lib "eagle-import") (part "NMOSREFLOW"))
    )
    (comp (ref "R1")
      (value "RESISTOR0805")
      (footprint "eagle-import:0805")
      (libsource (lib "eagle-import") (part "RESISTOR0805"))
    )
    (comp (ref "R3")
      (value "RESISTOR0805")
      (footprint "eagle-import:0805")
      (libsource (lib "eagle-import") (part "RESISTOR0805"))
    )
    (comp (ref "R5")
      (value "RESISTOR0805")
      (footprint "eagle-import:0805")
      (libsource (lib "eagle-import") (part "RESISTOR0805"))
    )
    (comp (ref "R7")
      (value "RESISTOR0805")
      (footprint "eagle-import:0805")
      (libsource (lib "eagle-import") (part "RESISTOR0805"))
    )
    (comp (ref "R9")
      (value "RESISTOR0805")
      (footprint "eagle-import:0805")
      (libsource (lib "eagle-import") (part "RESISTOR0805"))
    )
    (comp (ref "R11")
      (value "RESISTOR0805")
      (footprint "eagle-import:0805")
      (libsource (lib "eagle-import") (part "RESISTOR0805"))
    )
    (comp (ref "R13")
      (value "RESISTOR0805")
      (footprint "eagle-import:0805")
      (libsource (lib "eagle-import") (part "RESISTOR0805"))
    )
    (comp (ref "R15")
      (value "RESISTOR0805")
      (footprint "eagle-import:0805")
      (libsource (lib "eagle-import") (part "RESISTOR0805"))
    )
    (comp (ref "R17")
      (value "RESISTOR0805")
      (footprint "eagle-import:0805")
      (libsource (lib "eagle-import") (part "RESISTOR0805"))
    )
    (comp (ref "R19")
      (value "RESISTOR0805")
      (footprint "eagle-import:0805")
      (libsource (lib "eagle-import") (part "RESISTOR0805"))
    )
    (comp (ref "R21")
      (value "RESISTOR0805")
      (footprint "eagle-import:0805")
      (libsource (lib "eagle-import") (part "RESISTOR0805"))
    )
    (comp (ref "R23")
      (value "RESISTOR0805")
      (footprint "eagle-import:0805")
      (libsource (lib "eagle-import") (part "RESISTOR0805"))
    )
    (comp (ref "R25")
      (value "RESISTOR0805")
      (footprint "eagle-import:0805")
      (libsource (lib "eagle-import") (part "RESISTOR0805"))
    )
    (comp (ref "R27")
      (value "RESISTOR0805")
      (footprint "eagle-import:0805")
      (libsource (lib "eagle-import") (part "RESISTOR0805"))
    )
    (comp (ref "R29")
      (value "RESISTOR0805")
      (footprint "eagle-import:0805")
      (libsource (lib "eagle-import") (part "RESISTOR0805"))
    )
    (comp (ref "R31")
      (value "RESISTOR0805")
      (footprint "eagle-import:0805")
      (libsource (lib "eagle-import") (part "RESISTOR0805"))
    )
    (comp (ref "R33")
      (value "RESISTOR0805")
      (footprint "eagle-import:0805")
      (libsource (lib "eagle-import") (part "RESISTOR0805"))
    )
    (comp (ref "R34")
      (value "RESISTOR0805")
      (footprint "eagle-import:0805")
      (libsource (lib "eagle-import") (part "RESISTOR0805"))
    )
    (comp (ref "R35")
      (value "RESISTOR0805")
      (footprint "eagle-import:0805")
      (libsource (lib "eagle-import") (part "RESISTOR0805"))
    )
    (comp (ref "R36")
      (value "RESISTOR0805")
      (footprint "eagle-import:0805")
      (libsource (lib "eagle-import") (part "RESISTOR0805"))
    )
    (comp (ref "R37")
      (value "RESISTOR0805")
      (footprint "eagle-import:0805")
      (libsource (lib "eagle-import") (part "RESISTOR0805"))
    )
    (comp (ref "R38")
      (value "RESISTOR0805")
      (footprint "eagle-import:0805")
      (libsource (lib "eagle-import") (part "RESISTOR0805"))
    )
    (comp (ref "R39")
      (value "RESISTOR0805")
      (footprint "eagle-import:0805")
      (libsource (lib "eagle-import") (part "RESISTOR0805"))
    )
    (comp (ref "R40")
      (value "RESISTOR0805")
      (footprint "eagle-import:0805")
      (libsource (lib "eagle-import") (part "RESISTOR0805"))
    )
    (comp (ref "R41")
      (value "RESISTOR0805")
      (footprint "eagle-import:0805")
      (libsource (lib "eagle-import") (part "RESISTOR0805"))
    )
    (comp (ref "R42")
      (value "RESISTOR0805")
      (footprint "eagle-import:0805")
      (libsource (lib "eagle-import") (part "RESISTOR0805"))
    )
    (comp (ref "R43")
      (value "RESISTOR0805")
      (footprint "eagle-import:0805")
      (libsource (lib "eagle-import") (part "RESISTOR0805"))
    )
    (comp (ref "R44")
      (value "RESISTOR0805")
      (footprint "eagle-import:0805")
      (libsource (lib "eagle-import") (part "RESISTOR0805"))
    )
    (comp (ref "R45")
      (value "RESISTOR0805")
      (footprint "eagle-import:0805")
      (libsource (lib "eagle-import") (part "RESISTOR0805"))
    )
    (comp (ref "R46")
      (value "RESISTOR0805")
      (footprint "eagle-import:0805")
      (libsource (lib "eagle-import") (part "RESISTOR0805"))
    )
    (comp (ref "R47")
      (value "RESISTOR0805")
      (footprint "eagle-import:0805")
      (libsource (lib "eagle-import") (part "RESISTOR0805"))
    )
    (comp (ref "R48")
      (value "RESISTOR0805")
      (footprint "eagle-import:0805")
      (libsource (lib "eagle-import") (part "RESISTOR0805"))
    )
    (comp (ref "R65")
      (value "RESISTOR0805")
      (footprint "eagle-import:0805")
      (libsource (lib "eagle-import") (part "RESISTOR0805"))
    )
    (comp (ref "R66")
      (value "RESISTOR0805")
      (footprint "eagle-import:0805")
      (libsource (lib "eagle-import") (part "RESISTOR0805"))
    )
    (comp (ref "R67")
      (value "RESISTOR0805")
      (footprint "eagle-import:0805")
      (libsource (lib "eagle-import") (part "RESISTOR0805"))
    )
    (comp (ref "R68")
      (value "RESISTOR0805")
      (footprint "eagle-import:0805")
      (libsource (lib "eagle-import") (part "RESISTOR0805"))
    )
    (comp (ref "R69")
      (value "RESISTOR0805")
      (footprint "eagle-import:0805")
      (libsource (lib "eagle-import") (part "RESISTOR0805"))
    )
    (comp (ref "R70")
      (value "RESISTOR0805")
      (footprint "eagle-import:0805")
      (libsource (lib "eagle-import") (part "RESISTOR0805"))
    )
    (comp (ref "R71")
      (value "RESISTOR0805")
      (footprint "eagle-import:0805")
      (libsource (lib "eagle-import") (part "RESISTOR0805"))
    )
    (comp (ref "R72")
      (value "RESISTOR0805")
      (footprint "eagle-import:0805")
      (libsource (lib "eagle-import") (part "RESISTOR0805"))
    )
    (comp (ref "R73")
      (value "RESISTOR0805")
      (footprint "eagle-import:0805")
      (libsource (lib "eagle-import") (part "RESISTOR0805"))
    )
    (comp (ref "R74")
      (value "RESISTOR0805")
      (footprint "eagle-import:0805")
      (libsource (lib "eagle-import") (part "RESISTOR0805"))
    )
    (comp (ref "R75")
      (value "RESISTOR0805")
      (footprint "eagle-import:0805")
      (libsource (lib "eagle-import") (part "RESISTOR0805"))
    )
    (comp (ref "R76")
      (value "RESISTOR0805")
      (footprint "eagle-import:0805")
      (libsource (lib "eagle-import") (part "RESISTOR0805"))
    )
    (comp (ref "R77")
      (value "RESISTOR0805")
      (footprint "eagle-import:0805")
      (libsource (lib "eagle-import") (part "RESISTOR0805"))
    )
    (comp (ref "R78")
      (value "RESISTOR0805")
      (footprint "eagle-import:0805")
      (libsource (lib "eagle-import") (part "RESISTOR0805"))
    )
    (comp (ref "R79")
      (value "RESISTOR0805")
      (footprint "eagle-import:0805")
      (libsource (lib "eagle-import") (part "RESISTOR0805"))
    )
    (comp (ref "R80")
      (value "RESISTOR0805")
      (footprint "eagle-import:0805")
      (libsource (lib "eagle-import") (part "RESISTOR0805"))
    )
    (comp (ref "R97")
      (value "RESISTOR0805")
      (footprint "eagle-import:0805")
      (libsource (lib "eagle-import") (part "RESISTOR0805"))
    )
    (comp (ref "R98")
      (value "RESISTOR0805")
      (footprint "eagle-import:0805")
      (libsource (lib "eagle-import") (part "RESISTOR0805"))
    )
    (comp (ref "R99")
      (value "RESISTOR0805")
      (footprint "eagle-import:0805")
      (libsource (lib "eagle-import") (part "RESISTOR0805"))
    )
    (comp (ref "R100")
      (value "RESISTOR0805")
      (footprint "eagle-import:0805")
      (libsource (lib "eagle-import") (part "RESISTOR0805"))
    )
    (comp (ref "R101")
      (value "RESISTOR0805")
      (footprint "eagle-import:0805")
      (libsource (lib "eagle-import") (part "RESISTOR0805"))
    )
    (comp (ref "R102")
      (value "RESISTOR0805")
      (footprint "eagle-import:0805")
      (libsource (lib "eagle-import") (part "RESISTOR0805"))
    )
    (comp (ref "R103")
      (value "RESISTOR0805")
      (footprint "eagle-import:0805")
      (libsource (lib "eagle-import") (part "RESISTOR0805"))
    )
    (comp (ref "R104")
      (value "RESISTOR0805")
      (footprint "eagle-import:0805")
      (libsource (lib "eagle-import") (part "RESISTOR0805"))
    )
    (comp (ref "R105")
      (value "RESISTOR0805")
      (footprint "eagle-import:0805")
      (libsource (lib "eagle-import") (part "RESISTOR0805"))
    )
    (comp (ref "R106")
      (value "RESISTOR0805")
      (footprint "eagle-import:0805")
      (libsource (lib "eagle-import") (part "RESISTOR0805"))
    )
    (comp (ref "R107")
      (value "RESISTOR0805")
      (footprint "eagle-import:0805")
      (libsource (lib "eagle-import") (part "RESISTOR0805"))
    )
    (comp (ref "R108")
      (value "RESISTOR0805")
      (footprint "eagle-import:0805")
      (libsource (lib "eagle-import") (part "RESISTOR0805"))
    )
    (comp (ref "R109")
      (value "RESISTOR0805")
      (footprint "eagle-import:0805")
      (libsource (lib "eagle-import") (part "RESISTOR0805"))
    )
    (comp (ref "R110")
      (value "RESISTOR0805")
      (footprint "eagle-import:0805")
      (libsource (lib "eagle-import") (part "RESISTOR0805"))
    )
    (comp (ref "R111")
      (value "RESISTOR0805")
      (footprint "eagle-import:0805")
      (libsource (lib "eagle-import") (part "RESISTOR0805"))
    )
    (comp (ref "R112")
      (value "RESISTOR0805")
      (footprint "eagle-import:0805")
      (libsource (lib "eagle-import") (part "RESISTOR0805"))
    )
    (comp (ref "R129")
      (value "RESISTOR0805")
      (footprint "eagle-import:0805")
      (libsource (lib "eagle-import") (part "RESISTOR0805"))
    )
    (comp (ref "R130")
      (value "RESISTOR0805")
      (footprint "eagle-import:0805")
      (libsource (lib "eagle-import") (part "RESISTOR0805"))
    )
    (comp (ref "R131")
      (value "RESISTOR0805")
      (footprint "eagle-import:0805")
      (libsource (lib "eagle-import") (part "RESISTOR0805"))
    )
    (comp (ref "R132")
      (value "RESISTOR0805")
      (footprint "eagle-import:0805")
      (libsource (lib "eagle-import") (part "RESISTOR0805"))
    )
    (comp (ref "R133")
      (value "RESISTOR0805")
      (footprint "eagle-import:0805")
      (libsource (lib "eagle-import") (part "RESISTOR0805"))
    )
    (comp (ref "R134")
      (value "RESISTOR0805")
      (footprint "eagle-import:0805")
      (libsource (lib "eagle-import") (part "RESISTOR0805"))
    )
    (comp (ref "R135")
      (value "RESISTOR0805")
      (footprint "eagle-import:0805")
      (libsource (lib "eagle-import") (part "RESISTOR0805"))
    )
    (comp (ref "R136")
      (value "RESISTOR0805")
      (footprint "eagle-import:0805")
      (libsource (lib "eagle-import") (part "RESISTOR0805"))
    )
    (comp (ref "R137")
      (value "RESISTOR0805")
      (footprint "eagle-import:0805")
      (libsource (lib "eagle-import") (part "RESISTOR0805"))
    )
    (comp (ref "R138")
      (value "RESISTOR0805")
      (footprint "eagle-import:0805")
      (libsource (lib "eagle-import") (part "RESISTOR0805"))
    )
    (comp (ref "R139")
      (value "RESISTOR0805")
      (footprint "eagle-import:0805")
      (libsource (lib "eagle-import") (part "RESISTOR0805"))
    )
    (comp (ref "R140")
      (value "RESISTOR0805")
      (footprint "eagle-import:0805")
      (libsource (lib "eagle-import") (part "RESISTOR0805"))
    )
    (comp (ref "R141")
      (value "RESISTOR0805")
      (footprint "eagle-import:0805")
      (libsource (lib "eagle-import") (part "RESISTOR0805"))
    )
    (comp (ref "R142")
      (value "RESISTOR0805")
      (footprint "eagle-import:0805")
      (libsource (lib "eagle-import") (part "RESISTOR0805"))
    )
    (comp (ref "R143")
      (value "RESISTOR0805")
      (footprint "eagle-import:0805")
      (libsource (lib "eagle-import") (part "RESISTOR0805"))
    )
    (comp (ref "R144")
      (value "RESISTOR0805")
      (footprint "eagle-import:0805")
      (libsource (lib "eagle-import") (part "RESISTOR0805"))
    )
    (comp (ref "R161")
      (value "RESISTOR0805")
      (footprint "eagle-import:0805")
      (libsource (lib "eagle-import") (part "RESISTOR0805"))
    )
    (comp (ref "R162")
      (value "RESISTOR0805")
      (footprint "eagle-import:0805")
      (libsource (lib "eagle-import") (part "RESISTOR0805"))
    )
    (comp (ref "R163")
      (value "RESISTOR0805")
      (footprint "eagle-import:0805")
      (libsource (lib "eagle-import") (part "RESISTOR0805"))
    )
    (comp (ref "R164")
      (value "RESISTOR0805")
      (footprint "eagle-import:0805")
      (libsource (lib "eagle-import") (part "RESISTOR0805"))
    )
    (comp (ref "R165")
      (value "RESISTOR0805")
      (footprint "eagle-import:0805")
      (libsource (lib "eagle-import") (part "RESISTOR0805"))
    )
    (comp (ref "R166")
      (value "RESISTOR0805")
      (footprint "eagle-import:0805")
      (libsource (lib "eagle-import") (part "RESISTOR0805"))
    )
    (comp (ref "R167")
      (value "RESISTOR0805")
      (footprint "eagle-import:0805")
      (libsource (lib "eagle-import") (part "RESISTOR0805"))
    )
    (comp (ref "R168")
      (value "RESISTOR0805")
      (footprint "eagle-import:0805")
      (libsource (lib "eagle-import") (part "RESISTOR0805"))
    )
    (comp (ref "R169")
      (value "RESISTOR0805")
      (footprint "eagle-import:0805")
      (libsource (lib "eagle-import") (part "RESISTOR0805"))
    )
    (comp (ref "R170")
      (value "RESISTOR0805")
      (footprint "eagle-import:0805")
      (libsource (lib "eagle-import") (part "RESISTOR0805"))
    )
    (comp (ref "R171")
      (value "RESISTOR0805")
      (footprint "eagle-import:0805")
      (libsource (lib "eagle-import") (part "RESISTOR0805"))
    )
    (comp (ref "R172")
      (value "RESISTOR0805")
      (footprint "eagle-import:0805")
      (libsource (lib "eagle-import") (part "RESISTOR0805"))
    )
    (comp (ref "R173")
      (value "RESISTOR0805")
      (footprint "eagle-import:0805")
      (libsource (lib "eagle-import") (part "RESISTOR0805"))
    )
    (comp (ref "R174")
      (value "RESISTOR0805")
      (footprint "eagle-import:0805")
      (libsource (lib "eagle-import") (part "RESISTOR0805"))
    )
    (comp (ref "R175")
      (value "RESISTOR0805")
      (footprint "eagle-import:0805")
      (libsource (lib "eagle-import") (part "RESISTOR0805"))
    )
    (comp (ref "R176")
      (value "RESISTOR0805")
      (footprint "eagle-import:0805")
      (libsource (lib "eagle-import") (part "RESISTOR0805"))
    )
  )
  (nets
    (net (code "1") (name "/N$1") (class "Default")
      (node (ref "Q1") (pin "1") (pinfunction "G_1") (pintype "bidirectional"))
      (node (ref "Q129") (pin "1") (pinfunction "G_1") (pintype "bidirectional"))
      (node (ref "Q13") (pin "1") (pinfunction "G_1") (pintype "bidirectional"))
      (node (ref "Q131") (pin "1") (pinfunction "G_1") (pintype "bidirectional"))
      (node (ref "Q133") (pin "1") (pinfunction "G_1") (pintype "bidirectional"))
      (node (ref "Q135") (pin "1") (pinfunction "G_1") (pintype "bidirectional"))
      (node (ref "Q137") (pin "1") (pinfunction "G_1") (pintype "bidirectional"))
      (node (ref "Q139") (pin "1") (pinfunction "G_1") (pintype "bidirectional"))
      (node (ref "Q141") (pin "1") (pinfunction "G_1") (pintype "bidirectional"))
      (node (ref "Q143") (pin "1") (pinfunction "G_1") (pintype "bidirectional"))
      (node (ref "Q145") (pin "1") (pinfunction "G_1") (pintype "bidirectional"))
      (node (ref "Q147") (pin "1") (pinfunction "G_1") (pintype "bidirectional"))
      (node (ref "Q149") (pin "1") (pinfunction "G_1") (pintype "bidirectional"))
      (node (ref "Q151") (pin "1") (pinfunction "G_1") (pintype "bidirectional"))
      (node (ref "Q153") (pin "1") (pinfunction "G_1") (pintype "bidirectional"))
      (node (ref "Q155") (pin "1") (pinfunction "G_1") (pintype "bidirectional"))
      (node (ref "Q157") (pin "1") (pinfunction "G_1") (pintype "bidirectional"))
      (node (ref "Q159") (pin "1") (pinfunction "G_1") (pintype "bidirectional"))
      (node (ref "Q17") (pin "1") (pinfunction "G_1") (pintype "bidirectional"))
      (node (ref "Q193") (pin "1") (pinfunction "G_1") (pintype "bidirectional"))
      (node (ref "Q195") (pin "1") (pinfunction "G_1") (pintype "bidirectional"))
      (node (ref "Q197") (pin "1") (pinfunction "G_1") (pintype "bidirectional"))
      (node (ref "Q199") (pin "1") (pinfunction "G_1") (pintype "bidirectional"))
      (node (ref "Q201") (pin "1") (pinfunction "G_1") (pintype "bidirectional"))
      (node (ref "Q203") (pin "1") (pinfunction "G_1") (pintype "bidirectional"))
      (node (ref "Q205") (pin "1") (pinfunction "G_1") (pintype "bidirectional"))
      (node (ref "Q207") (pin "1") (pinfunction "G_1") (pintype "bidirectional"))
      (node (ref "Q209") (pin "1") (pinfunction "G_1") (pintype "bidirectional"))
      (node (ref "Q21") (pin "1") (pinfunction "G_1") (pintype "bidirectional"))
      (node (ref "Q211") (pin "1") (pinfunction "G_1") (pintype "bidirectional"))
      (node (ref "Q213") (pin "1") (pinfunction "G_1") (pintype "bidirectional"))
      (node (ref "Q215") (pin "1") (pinfunction "G_1") (pintype "bidirectional"))
      (node (ref "Q217") (pin "1") (pinfunction "G_1") (pintype "bidirectional"))
      (node (ref "Q219") (pin "1") (pinfunction "G_1") (pintype "bidirectional"))
      (node (ref "Q221") (pin "1") (pinfunction "G_1") (pintype "bidirectional"))
      (node (ref "Q223") (pin "1") (pinfunction "G_1") (pintype "bidirectional"))
      (node (ref "Q25") (pin "1") (pinfunction "G_1") (pintype "bidirectional"))
      (node (ref "Q257") (pin "1") (pinfunction "G_1") (pintype "bidirectional"))
      (node (ref "Q259") (pin "1") (pinfunction "G_1") (pintype "bidirectional"))
      (node (ref "Q261") (pin "1") (pinfunction "G_1") (pintype "bidirectional"))
      (node (ref "Q263") (pin "1") (pinfunction "G_1") (pintype "bidirectional"))
      (node (ref "Q265") (pin "1") (pinfunction "G_1") (pintype "bidirectional"))
      (node (ref "Q267") (pin "1") (pinfunction "G_1") (pintype "bidirectional"))
      (node (ref "Q269") (pin "1") (pinfunction "G_1") (pintype "bidirectional"))
      (node (ref "Q271") (pin "1") (pinfunction "G_1") (pintype "bidirectional"))
      (node (ref "Q273") (pin "1") (pinfunction "G_1") (pintype "bidirectional"))
      (node (ref "Q275") (pin "1") (pinfunction "G_1") (pintype "bidirectional"))
      (node (ref "Q277") (pin "1") (pinfunction "G_1") (pintype "bidirectional"))
      (node (ref "Q279") (pin "1") (pinfunction "G_1") (pintype "bidirectional"))
      (node (ref "Q281") (pin "1") (pinfunction "G_1") (pintype "bidirectional"))
      (node (ref "Q283") (pin "1") (pinfunction "G_1") (pintype "bidirectional"))
      (node (ref "Q285") (pin "1") (pinfunction "G_1") (pintype "bidirectional"))
      (node (ref "Q287") (pin "1") (pinfunction "G_1") (pintype "bidirectional"))
      (node (ref "Q29") (pin "1") (pinfunction "G_1") (pintype "bidirectional"))
      (node (ref "Q321") (pin "1") (pinfunction "G_1") (pintype "bidirectional"))
      (node (ref "Q323") (pin "1") (pinfunction "G_1") (pintype "bidirectional"))
      (node (ref "Q325") (pin "1") (pinfunction "G_1") (pintype "bidirectional"))
      (node (ref "Q327") (pin "1") (pinfunction "G_1") (pintype "bidirectional"))
      (node (ref "Q329") (pin "1") (pinfunction "G_1") (pintype "bidirectional"))
      (node (ref "Q33") (pin "1") (pinfunction "G_1") (pintype "bidirectional"))
      (node (ref "Q331") (pin "1") (pinfunction "G_1") (pintype "bidirectional"))
      (node (ref "Q333") (pin "1") (pinfunction "G_1") (pintype "bidirectional"))
      (node (ref "Q335") (pin "1") (pinfunction "G_1") (pintype "bidirectional"))
      (node (ref "Q337") (pin "1") (pinfunction "G_1") (pintype "bidirectional"))
      (node (ref "Q339") (pin "1") (pinfunction "G_1") (pintype "bidirectional"))
      (node (ref "Q341") (pin "1") (pinfunction "G_1") (pintype "bidirectional"))
      (node (ref "Q343") (pin "1") (pinfunction "G_1") (pintype "bidirectional"))
      (node (ref "Q345") (pin "1") (pinfunction "G_1") (pintype "bidirectional"))
      (node (ref "Q347") (pin "1") (pinfunction "G_1") (pintype "bidirectional"))
      (node (ref "Q349") (pin "1") (pinfunction "G_1") (pintype "bidirectional"))
      (node (ref "Q351") (pin "1") (pinfunction "G_1") (pintype "bidirectional"))
      (node (ref "Q37") (pin "1") (pinfunction "G_1") (pintype "bidirectional"))
      (node (ref "Q41") (pin "1") (pinfunction "G_1") (pintype "bidirectional"))
      (node (ref "Q45") (pin "1") (pinfunction "G_1") (pintype "bidirectional"))
      (node (ref "Q49") (pin "1") (pinfunction "G_1") (pintype "bidirectional"))
      (node (ref "Q5") (pin "1") (pinfunction "G_1") (pintype "bidirectional"))
      (node (ref "Q53") (pin "1") (pinfunction "G_1") (pintype "bidirectional"))
      (node (ref "Q57") (pin "1") (pinfunction "G_1") (pintype "bidirectional"))
      (node (ref "Q61") (pin "1") (pinfunction "G_1") (pintype "bidirectional"))
      (node (ref "Q65") (pin "1") (pinfunction "G_1") (pintype "bidirectional"))
      (node (ref "Q67") (pin "1") (pinfunction "G_1") (pintype "bidirectional"))
      (node (ref "Q69") (pin "1") (pinfunction "G_1") (pintype "bidirectional"))
      (node (ref "Q71") (pin "1") (pinfunction "G_1") (pintype "bidirectional"))
      (node (ref "Q73") (pin "1") (pinfunction "G_1") (pintype "bidirectional"))
      (node (ref "Q75") (pin "1") (pinfunction "G_1") (pintype "bidirectional"))
      (node (ref "Q77") (pin "1") (pinfunction "G_1") (pintype "bidirectional"))
      (node (ref "Q79") (pin "1") (pinfunction "G_1") (pintype "bidirectional"))
      (node (ref "Q81") (pin "1") (pinfunction "G_1") (pintype "bidirectional"))
      (node (ref "Q83") (pin "1") (pinfunction "G_1") (pintype "bidirectional"))
      (node (ref "Q85") (pin "1") (pinfunction "G_1") (pintype "bidirectional"))
      (node (ref "Q87") (pin "1") (pinfunction "G_1") (pintype "bidirectional"))
      (node (ref "Q89") (pin "1") (pinfunction "G_1") (pintype "bidirectional"))
      (node (ref "Q9") (pin "1") (pinfunction "G_1") (pintype "bidirectional"))
      (node (ref "Q91") (pin "1") (pinfunction "G_1") (pintype "bidirectional"))
      (node (ref "Q93") (pin "1") (pinfunction "G_1") (pintype "bidirectional"))
      (node (ref "Q95") (pin "1") (pinfunction "G_1") (pintype "bidirectional"))
    )
    (net (code "2") (name "/N$2") (class "Default")
      (node (ref "Q10") (pin "1") (pinfunction "G_1") (pintype "bidirectional"))
      (node (ref "Q130") (pin "1") (pinfunction "G_1") (pintype "bidirectional"))
      (node (ref "Q132") (pin "1") (pinfunction "G_1") (pintype "bidirectional"))
      (node (ref "Q134") (pin "1") (pinfunction "G_1") (pintype "bidirectional"))
      (node (ref "Q136") (pin "1") (pinfunction "G_1") (pintype "bidirectional"))
      (node (ref "Q138") (pin "1") (pinfunction "G_1") (pintype "bidirectional"))
      (node (ref "Q14") (pin "1") (pinfunction "G_1") (pintype "bidirectional"))
      (node (ref "Q140") (pin "1") (pinfunction "G_1") (pintype "bidirectional"))
      (node (ref "Q142") (pin "1") (pinfunction "G_1") (pintype "bidirectional"))
      (node (ref "Q144") (pin "1") (pinfunction "G_1") (pintype "bidirectional"))
      (node (ref "Q146") (pin "1") (pinfunction "G_1") (pintype "bidirectional"))
      (node (ref "Q148") (pin "1") (pinfunction "G_1") (pintype "bidirectional"))
      (node (ref "Q150") (pin "1") (pinfunction "G_1") (pintype "bidirectional"))
      (node (ref "Q152") (pin "1") (pinfunction "G_1") (pintype "bidirectional"))
      (node (ref "Q154") (pin "1") (pinfunction "G_1") (pintype "bidirectional"))
      (node (ref "Q156") (pin "1") (pinfunction "G_1") (pintype "bidirectional"))
      (node (ref "Q158") (pin "1") (pinfunction "G_1") (pintype "bidirectional"))
      (node (ref "Q160") (pin "1") (pinfunction "G_1") (pintype "bidirectional"))
      (node (ref "Q18") (pin "1") (pinfunction "G_1") (pintype "bidirectional"))
      (node (ref "Q194") (pin "1") (pinfunction "G_1") (pintype "bidirectional"))
      (node (ref "Q196") (pin "1") (pinfunction "G_1") (pintype "bidirectional"))
      (node (ref "Q198") (pin "1") (pinfunction "G_1") (pintype "bidirectional"))
      (node (ref "Q2") (pin "1") (pinfunction "G_1") (pintype "bidirectional"))
      (node (ref "Q200") (pin "1") (pinfunction "G_1") (pintype "bidirectional"))
      (node (ref "Q202") (pin "1") (pinfunction "G_1") (pintype "bidirectional"))
      (node (ref "Q204") (pin "1") (pinfunction "G_1") (pintype "bidirectional"))
      (node (ref "Q206") (pin "1") (pinfunction "G_1") (pintype "bidirectional"))
      (node (ref "Q208") (pin "1") (pinfunction "G_1") (pintype "bidirectional"))
      (node (ref "Q210") (pin "1") (pinfunction "G_1") (pintype "bidirectional"))
      (node (ref "Q212") (pin "1") (pinfunction "G_1") (pintype "bidirectional"))
      (node (ref "Q214") (pin "1") (pinfunction "G_1") (pintype "bidirectional"))
      (node (ref "Q216") (pin "1") (pinfunction "G_1") (pintype "bidirectional"))
      (node (ref "Q218") (pin "1") (pinfunction "G_1") (pintype "bidirectional"))
      (node (ref "Q22") (pin "1") (pinfunction "G_1") (pintype "bidirectional"))
      (node (ref "Q220") (pin "1") (pinfunction "G_1") (pintype "bidirectional"))
      (node (ref "Q222") (pin "1") (pinfunction "G_1") (pintype "bidirectional"))
      (node (ref "Q224") (pin "1") (pinfunction "G_1") (pintype "bidirectional"))
      (node (ref "Q258") (pin "1") (pinfunction "G_1") (pintype "bidirectional"))
      (node (ref "Q26") (pin "1") (pinfunction "G_1") (pintype "bidirectional"))
      (node (ref "Q260") (pin "1") (pinfunction "G_1") (pintype "bidirectional"))
      (node (ref "Q262") (pin "1") (pinfunction "G_1") (pintype "bidirectional"))
      (node (ref "Q264") (pin "1") (pinfunction "G_1") (pintype "bidirectional"))
      (node (ref "Q266") (pin "1") (pinfunction "G_1") (pintype "bidirectional"))
      (node (ref "Q268") (pin "1") (pinfunction "G_1") (pintype "bidirectional"))
      (node (ref "Q270") (pin "1") (pinfunction "G_1") (pintype "bidirectional"))
      (node (ref "Q272") (pin "1") (pinfunction "G_1") (pintype "bidirectional"))
      (node (ref "Q274") (pin "1") (pinfunction "G_1") (pintype "bidirectional"))
      (node (ref "Q276") (pin "1") (pinfunction "G_1") (pintype "bidirectional"))
      (node (ref "Q278") (pin "1") (pinfunction "G_1") (pintype "bidirectional"))
      (node (ref "Q280") (pin "1") (pinfunction "G_1") (pintype "bidirectional"))
      (node (ref "Q282") (pin "1") (pinfunction "G_1") (pintype "bidirectional"))
      (node (ref "Q284") (pin "1") (pinfunction "G_1") (pintype "bidirectional"))
      (node (ref "Q286") (pin "1") (pinfunction "G_1") (pintype "bidirectional"))
      (node (ref "Q288") (pin "1") (pinfunction "G_1") (pintype "bidirectional"))
      (node (ref "Q30") (pin "1") (pinfunction "G_1") (pintype "bidirectional"))
      (node (ref "Q322") (pin "1") (pinfunction "G_1") (pintype "bidirectional"))
      (node (ref "Q324") (pin "1") (pinfunction "G_1") (pintype "bidirectional"))
      (node (ref "Q326") (pin "1") (pinfunction "G_1") (pintype "bidirectional"))
      (node (ref "Q328") (pin "1") (pinfunction "G_1") (pintype "bidirectional"))
      (node (ref "Q330") (pin "1") (pinfunction "G_1") (pintype "bidirectional"))
      (node (ref "Q332") (pin "1") (pinfunction "G_1") (pintype "bidirectional"))
      (node (ref "Q334") (pin "1") (pinfunction "G_1") (pintype "bidirectional"))
      (node (ref "Q336") (pin "1") (pinfunction "G_1") (pintype "bidirectional"))
      (node (ref "Q338") (pin "1") (pinfunction "G_1") (pintype "bidirectional"))
      (node (ref "Q34") (pin "1") (pinfunction "G_1") (pintype "bidirectional"))
      (node (ref "Q340") (pin "1") (pinfunction "G_1") (pintype "bidirectional"))
      (node (ref "Q342") (pin "1") (pinfunction "G_1") (pintype "bidirectional"))
      (node (ref "Q344") (pin "1") (pinfunction "G_1") (pintype "bidirectional"))
      (node (ref "Q346") (pin "1") (pinfunction "G_1") (pintype "bidirectional"))
      (node (ref "Q348") (pin "1") (pinfunction "G_1") (pintype "bidirectional"))
      (node (ref "Q350") (pin "1") (pinfunction "G_1") (pintype "bidirectional"))
      (node (ref "Q352") (pin "1") (pinfunction "G_1") (pintype "bidirectional"))
      (node (ref "Q38") (pin "1") (pinfunction "G_1") (pintype "bidirectional"))
      (node (ref "Q42") (pin "1") (pinfunction "G_1") (pintype "bidirectional"))
      (node (ref "Q46") (pin "1") (pinfunction "G_1") (pintype "bidirectional"))
      (node (ref "Q50") (pin "1") (pinfunction "G_1") (pintype "bidirectional"))
      (node (ref "Q54") (pin "1") (pinfunction "G_1") (pintype "bidirectional"))
      (node (ref "Q58") (pin "1") (pinfunction "G_1") (pintype "bidirectional"))
      (node (ref "Q6") (pin "1") (pinfunction "G_1") (pintype "bidirectional"))
      (node (ref "Q62") (pin "1") (pinfunction "G_1") (pintype "bidirectional"))
      (node (ref "Q66") (pin "1") (pinfunction "G_1") (pintype "bidirectional"))
      (node (ref "Q68") (pin "1") (pinfunction "G_1") (pintype "bidirectional"))
      (node (ref "Q70") (pin "1") (pinfunction "G_1") (pintype "bidirectional"))
      (node (ref "Q72") (pin "1") (pinfunction "G_1") (pintype "bidirectional"))
      (node (ref "Q74") (pin "1") (pinfunction "G_1") (pintype "bidirectional"))
      (node (ref "Q76") (pin "1") (pinfunction "G_1") (pintype "bidirectional"))
      (node (ref "Q78") (pin "1") (pinfunction "G_1") (pintype "bidirectional"))
      (node (ref "Q80") (pin "1") (pinfunction "G_1") (pintype "bidirectional"))
      (node (ref "Q82") (pin "1") (pinfunction "G_1") (pintype "bidirectional"))
      (node (ref "Q84") (pin "1") (pinfunction "G_1") (pintype "bidirectional"))
      (node (ref "Q86") (pin "1") (pinfunction "G_1") (pintype "bidirectional"))
      (node (ref "Q88") (pin "1") (pinfunction "G_1") (pintype "bidirectional"))
      (node (ref "Q90") (pin "1") (pinfunction "G_1") (pintype "bidirectional"))
      (node (ref "Q92") (pin "1") (pinfunction "G_1") (pintype "bidirectional"))
      (node (ref "Q94") (pin "1") (pinfunction "G_1") (pintype "bidirectional"))
      (node (ref "Q96") (pin "1") (pinfunction "G_1") (pintype "bidirectional"))
    )
    (net (code "3") (name "/N$3") (class "Default")
      (node (ref "Q1") (pin "3") (pinfunction "D_3") (pintype "bidirectional"))
      (node (ref "Q10") (pin "3") (pinfunction "D_3") (pintype "bidirectional"))
      (node (ref "Q129") (pin "3") (pinfunction "D_3") (pintype "bidirectional"))
      (node (ref "Q13") (pin "3") (pinfunction "D_3") (pintype "bidirectional"))
      (node (ref "Q130") (pin "3") (pinfunction "D_3") (pintype "bidirectional"))
      (node (ref "Q131") (pin "3") (pinfunction "D_3") (pintype "bidirectional"))
      (node (ref "Q132") (pin "3") (pinfunction "D_3") (pintype "bidirectional"))
      (node (ref "Q133") (pin "3") (pinfunction "D_3") (pintype "bidirectional"))
      (node (ref "Q134") (pin "3") (pinfunction "D_3") (pintype "bidirectional"))
      (node (ref "Q135") (pin "3") (pinfunction "D_3") (pintype "bidirectional"))
      (node (ref "Q136") (pin "3") (pinfunction "D_3") (pintype "bidirectional"))
      (node (ref "Q137") (pin "3") (pinfunction "D_3") (pintype "bidirectional"))
      (node (ref "Q138") (pin "3") (pinfunction "D_3") (pintype "bidirectional"))
      (node (ref "Q139") (pin "3") (pinfunction "D_3") (pintype "bidirectional"))
      (node (ref "Q14") (pin "3") (pinfunction "D_3") (pintype "bidirectional"))
      (node (ref "Q140") (pin "3") (pinfunction "D_3") (pintype "bidirectional"))
      (node (ref "Q141") (pin "3") (pinfunction "D_3") (pintype "bidirectional"))
      (node (ref "Q142") (pin "3") (pinfunction "D_3") (pintype "bidirectional"))
      (node (ref "Q143") (pin "3") (pinfunction "D_3") (pintype "bidirectional"))
      (node (ref "Q144") (pin "3") (pinfunction "D_3") (pintype "bidirectional"))
      (node (ref "Q145") (pin "3") (pinfunction "D_3") (pintype "bidirectional"))
      (node (ref "Q146") (pin "3") (pinfunction "D_3") (pintype "bidirectional"))
      (node (ref "Q147") (pin "3") (pinfunction "D_3") (pintype "bidirectional"))
      (node (ref "Q148") (pin "3") (pinfunction "D_3") (pintype "bidirectional"))
      (node (ref "Q149") (pin "3") (pinfunction "D_3") (pintype "bidirectional"))
      (node (ref "Q150") (pin "3") (pinfunction "D_3") (pintype "bidirectional"))
      (node (ref "Q151") (pin "3") (pinfunction "D_3") (pintype "bidirectional"))
      (node (ref "Q152") (pin "3") (pinfunction "D_3") (pintype "bidirectional"))
      (node (ref "Q153") (pin "3") (pinfunction "D_3") (pintype "bidirectional"))
      (node (ref "Q154") (pin "3") (pinfunction "D_3") (pintype "bidirectional"))
      (node (ref "Q155") (pin "3") (pinfunction "D_3") (pintype "bidirectional"))
      (node (ref "Q156") (pin "3") (pinfunction "D_3") (pintype "bidirectional"))
      (node (ref "Q157") (pin "3") (pinfunction "D_3") (pintype "bidirectional"))
      (node (ref "Q158") (pin "3") (pinfunction "D_3") (pintype "bidirectional"))
      (node (ref "Q159") (pin "3") (pinfunction "D_3") (pintype "bidirectional"))
      (node (ref "Q160") (pin "3") (pinfunction "D_3") (pintype "bidirectional"))
      (node (ref "Q17") (pin "3") (pinfunction "D_3") (pintype "bidirectional"))
      (node (ref "Q18") (pin "3") (pinfunction "D_3") (pintype "bidirectional"))
      (node (ref "Q193") (pin "3") (pinfunction "D_3") (pintype "bidirectional"))
      (node (ref "Q194") (pin "3") (pinfunction "D_3") (pintype "bidirectional"))
      (node (ref "Q195") (pin "3") (pinfunction "D_3") (pintype "bidirectional"))
      (node (ref "Q196") (pin "3") (pinfunction "D_3") (pintype "bidirectional"))
      (node (ref "Q197") (pin "3") (pinfunction "D_3") (pintype "bidirectional"))
      (node (ref "Q198") (pin "3") (pinfunction "D_3") (pintype "bidirectional"))
      (node (ref "Q199") (pin "3") (pinfunction "D_3") (pintype "bidirectional"))
      (node (ref "Q2") (pin "3") (pinfunction "D_3") (pintype "bidirectional"))
      (node (ref "Q200") (pin "3") (pinfunction "D_3") (pintype "bidirectional"))
      (node (ref "Q201") (pin "3") (pinfunction "D_3") (pintype "bidirectional"))
      (node (ref "Q202") (pin "3") (pinfunction "D_3") (pintype "bidirectional"))
      (node (ref "Q203") (pin "3") (pinfunction "D_3") (pintype "bidirectional"))
      (node (ref "Q204") (pin "3") (pinfunction "D_3") (pintype "bidirectional"))
      (node (ref "Q205") (pin "3") (pinfunction "D_3") (pintype "bidirectional"))
      (node (ref "Q206") (pin "3") (pinfunction "D_3") (pintype "bidirectional"))
      (node (ref "Q207") (pin "3") (pinfunction "D_3") (pintype "bidirectional"))
      (node (ref "Q208") (pin "3") (pinfunction "D_3") (pintype "bidirectional"))
      (node (ref "Q209") (pin "3") (pinfunction "D_3") (pintype "bidirectional"))
      (node (ref "Q21") (pin "3") (pinfunction "D_3") (pintype "bidirectional"))
      (node (ref "Q210") (pin "3") (pinfunction "D_3") (pintype "bidirectional"))
      (node (ref "Q211") (pin "3") (pinfunction "D_3") (pintype "bidirectional"))
      (node (ref "Q212") (pin "3") (pinfunction "D_3") (pintype "bidirectional"))
      (node (ref "Q213") (pin "3") (pinfunction "D_3") (pintype "bidirectional"))
      (node (ref "Q214") (pin "3") (pinfunction "D_3") (pintype "bidirectional"))
      (node (ref "Q215") (pin "3") (pinfunction "D_3") (pintype "bidirectional"))
      (node (ref "Q216") (pin "3") (pinfunction "D_3") (pintype "bidirectional"))
      (node (ref "Q217") (pin "3") (pinfunction "D_3") (pintype "bidirectional"))
      (node (ref "Q218") (pin "3") (pinfunction "D_3") (pintype "bidirectional"))
      (node (ref "Q219") (pin "3") (pinfunction "D_3") (pintype "bidirectional"))
      (node (ref "Q22") (pin "3") (pinfunction "D_3") (pintype "bidirectional"))
      (node (ref "Q220") (pin "3") (pinfunction "D_3") (pintype "bidirectional"))
      (node (ref "Q221") (pin "3") (pinfunction "D_3") (pintype "bidirectional"))
      (node (ref "Q222") (pin "3") (pinfunction "D_3") (pintype "bidirectional"))
      (node (ref "Q223") (pin "3") (pinfunction "D_3") (pintype "bidirectional"))
      (node (ref "Q224") (pin "3") (pinfunction "D_3") (pintype "bidirectional"))
      (node (ref "Q25") (pin "3") (pinfunction "D_3") (pintype "bidirectional"))
      (node (ref "Q257") (pin "3") (pinfunction "D_3") (pintype "bidirectional"))
      (node (ref "Q258") (pin "3") (pinfunction "D_3") (pintype "bidirectional"))
      (node (ref "Q259") (pin "3") (pinfunction "D_3") (pintype "bidirectional"))
      (node (ref "Q26") (pin "3") (pinfunction "D_3") (pintype "bidirectional"))
      (node (ref "Q260") (pin "3") (pinfunction "D_3") (pintype "bidirectional"))
      (node (ref "Q261") (pin "3") (pinfunction "D_3") (pintype "bidirectional"))
      (node (ref "Q262") (pin "3") (pinfunction "D_3") (pintype "bidirectional"))
      (node (ref "Q263") (pin "3") (pinfunction "D_3") (pintype "bidirectional"))
      (node (ref "Q264") (pin "3") (pinfunction "D_3") (pintype "bidirectional"))
      (node (ref "Q265") (pin "3") (pinfunction "D_3") (pintype "bidirectional"))
      (node (ref "Q266") (pin "3") (pinfunction "D_3") (pintype "bidirectional"))
      (node (ref "Q267") (pin "3") (pinfunction "D_3") (pintype "bidirectional"))
      (node (ref "Q268") (pin "3") (pinfunction "D_3") (pintype "bidirectional"))
      (node (ref "Q269") (pin "3") (pinfunction "D_3") (pintype "bidirectional"))
      (node (ref "Q270") (pin "3") (pinfunction "D_3") (pintype "bidirectional"))
      (node (ref "Q271") (pin "3") (pinfunction "D_3") (pintype "bidirectional"))
      (node (ref "Q272") (pin "3") (pinfunction "D_3") (pintype "bidirectional"))
      (node (ref "Q273") (pin "3") (pinfunction "D_3") (pintype "bidirectional"))
      (node (ref "Q274") (pin "3") (pinfunction "D_3") (pintype "bidirectional"))
      (node (ref "Q275") (pin "3") (pinfunction "D_3") (pintype "bidirectional"))
      (node (ref "Q276") (pin "3") (pinfunction "D_3") (pintype "bidirectional"))
      (node (ref "Q277") (pin "3") (pinfunction "D_3") (pintype "bidirectional"))
      (node (ref "Q278") (pin "3") (pinfunction "D_3") (pintype "bidirectional"))
      (node (ref "Q279") (pin "3") (pinfunction "D_3") (pintype "bidirectional"))
      (node (ref "Q280") (pin "3") (pinfunction "D_3") (pintype "bidirectional"))
      (node (ref "Q281") (pin "3") (pinfunction "D_3") (pintype "bidirectional"))
      (node (ref "Q282") (pin "3") (pinfunction "D_3") (pintype "bidirectional"))
      (node (ref "Q283") (pin "3") (pinfunction "D_3") (pintype "bidirectional"))
      (node (ref "Q284") (pin "3") (pinfunction "D_3") (pintype "bidirectional"))
      (node (ref "Q285") (pin "3") (pinfunction "D_3") (pintype "bidirectional"))
      (node (ref "Q286") (pin "3") (pinfunction "D_3") (pintype "bidirectional"))
      (node (ref "Q287") (pin "3") (pinfunction "D_3") (pintype "bidirectional"))
      (node (ref "Q288") (pin "3") (pinfunction "D_3") (pintype "bidirectional"))
      (node (ref "Q29") (pin "3") (pinfunction "D_3") (pintype "bidirectional"))
      (node (ref "Q30") (pin "3") (pinfunction "D_3") (pintype "bidirectional"))
      (node (ref "Q321") (pin "3") (pinfunction "D_3") (pintype "bidirectional"))
      (node (ref "Q322") (pin "3") (pinfunction "D_3") (pintype "bidirectional"))
      (node (ref "Q323") (pin "3") (pinfunction "D_3") (pintype "bidirectional"))
      (node (ref "Q324") (pin "3") (pinfunction "D_3") (pintype "bidirectional"))
      (node (ref "Q325") (pin "3") (pinfunction "D_3") (pintype "bidirectional"))
      (node (ref "Q326") (pin "3") (pinfunction "D_3") (pintype "bidirectional"))
      (node (ref "Q327") (pin "3") (pinfunction "D_3") (pintype "bidirectional"))
      (node (ref "Q328") (pin "3") (pinfunction "D_3") (pintype "bidirectional"))
      (node (ref "Q329") (pin "3") (pinfunction "D_3") (pintype "bidirectional"))
      (node (ref "Q33") (pin "3") (pinfunction "D_3") (pintype "bidirectional"))
      (node (ref "Q330") (pin "3") (pinfunction "D_3") (pintype "bidirectional"))
      (node (ref "Q331") (pin "3") (pinfunction "D_3") (pintype "bidirectional"))
      (node (ref "Q332") (pin "3") (pinfunction "D_3") (pintype "bidirectional"))
      (node (ref "Q333") (pin "3") (pinfunction "D_3") (pintype "bidirectional"))
      (node (ref "Q334") (pin "3") (pinfunction "D_3") (pintype "bidirectional"))
      (node (ref "Q335") (pin "3") (pinfunction "D_3") (pintype "bidirectional"))
      (node (ref "Q336") (pin "3") (pinfunction "D_3") (pintype "bidirectional"))
      (node (ref "Q337") (pin "3") (pinfunction "D_3") (pintype "bidirectional"))
      (node (ref "Q338") (pin "3") (pinfunction "D_3") (pintype "bidirectional"))
      (node (ref "Q339") (pin "3") (pinfunction "D_3") (pintype "bidirectional"))
      (node (ref "Q34") (pin "3") (pinfunction "D_3") (pintype "bidirectional"))
      (node (ref "Q340") (pin "3") (pinfunction "D_3") (pintype "bidirectional"))
      (node (ref "Q341") (pin "3") (pinfunction "D_3") (pintype "bidirectional"))
      (node (ref "Q342") (pin "3") (pinfunction "D_3") (pintype "bidirectional"))
      (node (ref "Q343") (pin "3") (pinfunction "D_3") (pintype "bidirectional"))
      (node (ref "Q344") (pin "3") (pinfunction "D_3") (pintype "bidirectional"))
      (node (ref "Q345") (pin "3") (pinfunction "D_3") (pintype "bidirectional"))
      (node (ref "Q346") (pin "3") (pinfunction "D_3") (pintype "bidirectional"))
      (node (ref "Q347") (pin "3") (pinfunction "D_3") (pintype "bidirectional"))
      (node (ref "Q348") (pin "3") (pinfunction "D_3") (pintype "bidirectional"))
      (node (ref "Q349") (pin "3") (pinfunction "D_3") (pintype "bidirectional"))
      (node (ref "Q350") (pin "3") (pinfunction "D_3") (pintype "bidirectional"))
      (node (ref "Q351") (pin "3") (pinfunction "D_3") (pintype "bidirectional"))
      (node (ref "Q352") (pin "3") (pinfunction "D_3") (pintype "bidirectional"))
      (node (ref "Q37") (pin "3") (pinfunction "D_3") (pintype "bidirectional"))
      (node (ref "Q38") (pin "3") (pinfunction "D_3") (pintype "bidirectional"))
      (node (ref "Q41") (pin "3") (pinfunction "D_3") (pintype "bidirectional"))
      (node (ref "Q42") (pin "3") (pinfunction "D_3") (pintype "bidirectional"))
      (node (ref "Q45") (pin "3") (pinfunction "D_3") (pintype "bidirectional"))
      (node (ref "Q46") (pin "3") (pinfunction "D_3") (pintype "bidirectional"))
      (node (ref "Q49") (pin "3") (pinfunction "D_3") (pintype "bidirectional"))
      (node (ref "Q5") (pin "3") (pinfunction "D_3") (pintype "bidirectional"))
      (node (ref "Q50") (pin "3") (pinfunction "D_3") (pintype "bidirectional"))
      (node (ref "Q53") (pin "3") (pinfunction "D_3") (pintype "bidirectional"))
      (node (ref "Q54") (pin "3") (pinfunction "D_3") (pintype "bidirectional"))
      (node (ref "Q57") (pin "3") (pinfunction "D_3") (pintype "bidirectional"))
      (node (ref "Q58") (pin "3") (pinfunction "D_3") (pintype "bidirectional"))
      (node (ref "Q6") (pin "3") (pinfunction "D_3") (pintype "bidirectional"))
      (node (ref "Q61") (pin "3") (pinfunction "D_3") (pintype "bidirectional"))
      (node (ref "Q62") (pin "3") (pinfunction "D_3") (pintype "bidirectional"))
      (node (ref "Q65") (pin "3") (pinfunction "D_3") (pintype "bidirectional"))
      (node (ref "Q66") (pin "3") (pinfunction "D_3") (pintype "bidirectional"))
      (node (ref "Q67") (pin "3") (pinfunction "D_3") (pintype "bidirectional"))
      (node (ref "Q68") (pin "3") (pinfunction "D_3") (pintype "bidirectional"))
      (node (ref "Q69") (pin "3") (pinfunction "D_3") (pintype "bidirectional"))
      (node (ref "Q70") (pin "3") (pinfunction "D_3") (pintype "bidirectional"))
      (node (ref "Q71") (pin "3") (pinfunction "D_3") (pintype "bidirectional"))
      (node (ref "Q72") (pin "3") (pinfunction "D_3") (pintype "bidirectional"))
      (node (ref "Q73") (pin "3") (pinfunction "D_3") (pintype "bidirectional"))
      (node (ref "Q74") (pin "3") (pinfunction "D_3") (pintype "bidirectional"))
      (node (ref "Q75") (pin "3") (pinfunction "D_3") (pintype "bidirectional"))
      (node (ref "Q76") (pin "3") (pinfunction "D_3") (pintype "bidirectional"))
      (node (ref "Q77") (pin "3") (pinfunction "D_3") (pintype "bidirectional"))
      (node (ref "Q78") (pin "3") (pinfunction "D_3") (pintype "bidirectional"))
      (node (ref "Q79") (pin "3") (pinfunction "D_3") (pintype "bidirectional"))
      (node (ref "Q80") (pin "3") (pinfunction "D_3") (pintype "bidirectional"))
      (node (ref "Q81") (pin "3") (pinfunction "D_3") (pintype "bidirectional"))
      (node (ref "Q82") (pin "3") (pinfunction "D_3") (pintype "bidirectional"))
      (node (ref "Q83") (pin "3") (pinfunction "D_3") (pintype "bidirectional"))
      (node (ref "Q84") (pin "3") (pinfunction "D_3") (pintype "bidirectional"))
      (node (ref "Q85") (pin "3") (pinfunction "D_3") (pintype "bidirectional"))
      (node (ref "Q86") (pin "3") (pinfunction "D_3") (pintype "bidirectional"))
      (node (ref "Q87") (pin "3") (pinfunction "D_3") (pintype "bidirectional"))
      (node (ref "Q88") (pin "3") (pinfunction "D_3") (pintype "bidirectional"))
      (node (ref "Q89") (pin "3") (pinfunction "D_3") (pintype "bidirectional"))
      (node (ref "Q9") (pin "3") (pinfunction "D_3") (pintype "bidirectional"))
      (node (ref "Q90") (pin "3") (pinfunction "D_3") (pintype "bidirectional"))
      (node (ref "Q91") (pin "3") (pinfunction "D_3") (pintype "bidirectional"))
      (node (ref "Q92") (pin "3") (pinfunction "D_3") (pintype "bidirectional"))
      (node (ref "Q93") (pin "3") (pinfunction "D_3") (pintype "bidirectional"))
      (node (ref "Q94") (pin "3") (pinfunction "D_3") (pintype "bidirectional"))
      (node (ref "Q95") (pin "3") (pinfunction "D_3") (pintype "bidirectional"))
      (node (ref "Q96") (pin "3") (pinfunction "D_3") (pintype "bidirectional"))
      (node (ref "R1") (pin "2") (pinfunction "2_2") (pintype "passive"))
      (node (ref "R100") (pin "2") (pinfunction "2_2") (pintype "passive"))
      (node (ref "R101") (pin "2") (pinfunction "2_2") (pintype "passive"))
      (node (ref "R102") (pin "2") (pinfunction "2_2") (pintype "passive"))
      (node (ref "R103") (pin "2") (pinfunction "2_2") (pintype "passive"))
      (node (ref "R104") (pin "2") (pinfunction "2_2") (pintype "passive"))
      (node (ref "R105") (pin "2") (pinfunction "2_2") (pintype "passive"))
      (node (ref "R106") (pin "2") (pinfunction "2_2") (pintype "passive"))
      (node (ref "R107") (pin "2") (pinfunction "2_2") (pintype "passive"))
      (node (ref "R108") (pin "2") (pinfunction "2_2") (pintype "passive"))
      (node (ref "R109") (pin "2") (pinfunction "2_2") (pintype "passive"))
      (node (ref "R11") (pin "2") (pinfunction "2_2") (pintype "passive"))
      (node (ref "R110") (pin "2") (pinfunction "2_2") (pintype "passive"))
      (node (ref "R111") (pin "2") (pinfunction "2_2") (pintype "passive"))
      (node (ref "R112") (pin "2") (pinfunction "2_2") (pintype "passive"))
      (node (ref "R129") (pin "2") (pinfunction "2_2") (pintype "passive"))
      (node (ref "R13") (pin "2") (pinfunction "2_2") (pintype "passive"))
      (node (ref "R130") (pin "2") (pinfunction "2_2") (pintype "passive"))
      (node (ref "R131") (pin "2") (pinfunction "2_2") (pintype "passive"))
      (node (ref "R132") (pin "2") (pinfunction "2_2") (pintype "passive"))
      (node (ref "R133") (pin "2") (pinfunction "2_2") (pintype "passive"))
      (node (ref "R134") (pin "2") (pinfunction "2_2") (pintype "passive"))
      (node (ref "R135") (pin "2") (pinfunction "2_2") (pintype "passive"))
      (node (ref "R136") (pin "2") (pinfunction "2_2") (pintype "passive"))
      (node (ref "R137") (pin "2") (pinfunction "2_2") (pintype "passive"))
      (node (ref "R138") (pin "2") (pinfunction "2_2") (pintype "passive"))
      (node (ref "R139") (pin "2") (pinfunction "2_2") (pintype "passive"))
      (node (ref "R140") (pin "2") (pinfunction "2_2") (pintype "passive"))
      (node (ref "R141") (pin "2") (pinfunction "2_2") (pintype "passive"))
      (node (ref "R142") (pin "2") (pinfunction "2_2") (pintype "passive"))
      (node (ref "R143") (pin "2") (pinfunction "2_2") (pintype "passive"))
      (node (ref "R144") (pin "2") (pinfunction "2_2") (pintype "passive"))
      (node (ref "R15") (pin "2") (pinfunction "2_2") (pintype "passive"))
      (node (ref "R161") (pin "2") (pinfunction "2_2") (pintype "passive"))
      (node (ref "R162") (pin "2") (pinfunction "2_2") (pintype "passive"))
      (node (ref "R163") (pin "2") (pinfunction "2_2") (pintype "passive"))
      (node (ref "R164") (pin "2") (pinfunction "2_2") (pintype "passive"))
      (node (ref "R165") (pin "2") (pinfunction "2_2") (pintype "passive"))
      (node (ref "R166") (pin "2") (pinfunction "2_2") (pintype "passive"))
      (node (ref "R167") (pin "2") (pinfunction "2_2") (pintype "passive"))
      (node (ref "R168") (pin "2") (pinfunction "2_2") (pintype "passive"))
      (node (ref "R169") (pin "2") (pinfunction "2_2") (pintype "passive"))
      (node (ref "R17") (pin "2") (pinfunction "2_2") (pintype "passive"))
      (node (ref "R170") (pin "2") (pinfunction "2_2") (pintype "passive"))
      (node (ref "R171") (pin "2") (pinfunction "2_2") (pintype "passive"))
      (node (ref "R172") (pin "2") (pinfunction "2_2") (pintype "passive"))
      (node (ref "R173") (pin "2") (pinfunction "2_2") (pintype "passive"))
      (node (ref "R174") (pin "2") (pinfunction "2_2") (pintype "passive"))
      (node (ref "R175") (pin "2") (pinfunction "2_2") (pintype "passive"))
      (node (ref "R176") (pin "2") (pinfunction "2_2") (pintype "passive"))
      (node (ref "R19") (pin "2") (pinfunction "2_2") (pintype "passive"))
      (node (ref "R21") (pin "2") (pinfunction "2_2") (pintype "passive"))
      (node (ref "R23") (pin "2") (pinfunction "2_2") (pintype "passive"))
      (node (ref "R25") (pin "2") (pinfunction "2_2") (pintype "passive"))
      (node (ref "R27") (pin "2") (pinfunction "2_2") (pintype "passive"))
      (node (ref "R29") (pin "2") (pinfunction "2_2") (pintype "passive"))
      (node (ref "R3") (pin "2") (pinfunction "2_2") (pintype "passive"))
      (node (ref "R31") (pin "2") (pinfunction "2_2") (pintype "passive"))
      (node (ref "R33") (pin "2") (pinfunction "2_2") (pintype "passive"))
      (node (ref "R34") (pin "2") (pinfunction "2_2") (pintype "passive"))
      (node (ref "R35") (pin "2") (pinfunction "2_2") (pintype "passive"))
      (node (ref "R36") (pin "2") (pinfunction "2_2") (pintype "passive"))
      (node (ref "R37") (pin "2") (pinfunction "2_2") (pintype "passive"))
      (node (ref "R38") (pin "2") (pinfunction "2_2") (pintype "passive"))
      (node (ref "R39") (pin "2") (pinfunction "2_2") (pintype "passive"))
      (node (ref "R40") (pin "2") (pinfunction "2_2") (pintype "passive"))
      (node (ref "R41") (pin "2") (pinfunction "2_2") (pintype "passive"))
      (node (ref "R42") (pin "2") (pinfunction "2_2") (pintype "passive"))
      (node (ref "R43") (pin "2") (pinfunction "2_2") (pintype "passive"))
      (node (ref "R44") (pin "2") (pinfunction "2_2") (pintype "passive"))
      (node (ref "R45") (pin "2") (pinfunction "2_2") (pintype "passive"))
      (node (ref "R46") (pin "2") (pinfunction "2_2") (pintype "passive"))
      (node (ref "R47") (pin "2") (pinfunction "2_2") (pintype "passive"))
      (node (ref "R48") (pin "2") (pinfunction "2_2") (pintype "passive"))
      (node (ref "R5") (pin "2") (pinfunction "2_2") (pintype "passive"))
      (node (ref "R65") (pin "2") (pinfunction "2_2") (pintype "passive"))
      (node (ref "R66") (pin "2") (pinfunction "2_2") (pintype "passive"))
      (node (ref "R67") (pin "2") (pinfunction "2_2") (pintype "passive"))
      (node (ref "R68") (pin "2") (pinfunction "2_2") (pintype "passive"))
      (node (ref "R69") (pin "2") (pinfunction "2_2") (pintype "passive"))
      (node (ref "R7") (pin "2") (pinfunction "2_2") (pintype "passive"))
      (node (ref "R70") (pin "2") (pinfunction "2_2") (pintype "passive"))
      (node (ref "R71") (pin "2") (pinfunction "2_2") (pintype "passive"))
      (node (ref "R72") (pin "2") (pinfunction "2_2") (pintype "passive"))
      (node (ref "R73") (pin "2") (pinfunction "2_2") (pintype "passive"))
      (node (ref "R74") (pin "2") (pinfunction "2_2") (pintype "passive"))
      (node (ref "R75") (pin "2") (pinfunction "2_2") (pintype "passive"))
      (node (ref "R76") (pin "2") (pinfunction "2_2") (pintype "passive"))
      (node (ref "R77") (pin "2") (pinfunction "2_2") (pintype "passive"))
      (node (ref "R78") (pin "2") (pinfunction "2_2") (pintype "passive"))
      (node (ref "R79") (pin "2") (pinfunction "2_2") (pintype "passive"))
      (node (ref "R80") (pin "2") (pinfunction "2_2") (pintype "passive"))
      (node (ref "R9") (pin "2") (pinfunction "2_2") (pintype "passive"))
      (node (ref "R97") (pin "2") (pinfunction "2_2") (pintype "passive"))
      (node (ref "R98") (pin "2") (pinfunction "2_2") (pintype "passive"))
      (node (ref "R99") (pin "2") (pinfunction "2_2") (pintype "passive"))
    )
    (net (code "4") (name "GND") (class "Default")
      (node (ref "C10") (pin "2") (pinfunction "2_2") (pintype "passive"))
      (node (ref "C12") (pin "2") (pinfunction "2_2") (pintype "passive"))
      (node (ref "C14") (pin "2") (pinfunction "2_2") (pintype "passive"))
      (node (ref "C16") (pin "2") (pinfunction "2_2") (pintype "passive"))
      (node (ref "C2") (pin "2") (pinfunction "2_2") (pintype "passive"))
      (node (ref "C4") (pin "2") (pinfunction "2_2") (pintype "passive"))
      (node (ref "C6") (pin "2") (pinfunction "2_2") (pintype "passive"))
      (node (ref "C8") (pin "2") (pinfunction "2_2") (pintype "passive"))
      (node (ref "JP2") (pin "30") (pinfunction "30_30") (pintype "passive"))
      (node (ref "Q1") (pin "2") (pinfunction "S_2") (pintype "bidirectional"))
      (node (ref "Q10") (pin "2") (pinfunction "S_2") (pintype "bidirectional"))
      (node (ref "Q129") (pin "2") (pinfunction "S_2") (pintype "bidirectional"))
      (node (ref "Q13") (pin "2") (pinfunction "S_2") (pintype "bidirectional"))
      (node (ref "Q130") (pin "2") (pinfunction "S_2") (pintype "bidirectional"))
      (node (ref "Q131") (pin "2") (pinfunction "S_2") (pintype "bidirectional"))
      (node (ref "Q132") (pin "2") (pinfunction "S_2") (pintype "bidirectional"))
      (node (ref "Q133") (pin "2") (pinfunction "S_2") (pintype "bidirectional"))
      (node (ref "Q134") (pin "2") (pinfunction "S_2") (pintype "bidirectional"))
      (node (ref "Q135") (pin "2") (pinfunction "S_2") (pintype "bidirectional"))
      (node (ref "Q136") (pin "2") (pinfunction "S_2") (pintype "bidirectional"))
      (node (ref "Q137") (pin "2") (pinfunction "S_2") (pintype "bidirectional"))
      (node (ref "Q138") (pin "2") (pinfunction "S_2") (pintype "bidirectional"))
      (node (ref "Q139") (pin "2") (pinfunction "S_2") (pintype "bidirectional"))
      (node (ref "Q14") (pin "2") (pinfunction "S_2") (pintype "bidirectional"))
      (node (ref "Q140") (pin "2") (pinfunction "S_2") (pintype "bidirectional"))
      (node (ref "Q141") (pin "2") (pinfunction "S_2") (pintype "bidirectional"))
      (node (ref "Q142") (pin "2") (pinfunction "S_2") (pintype "bidirectional"))
      (node (ref "Q143") (pin "2") (pinfunction "S_2") (pintype "bidirectional"))
      (node (ref "Q144") (pin "2") (pinfunction "S_2") (pintype "bidirectional"))
      (node (ref "Q145") (pin "2") (pinfunction "S_2") (pintype "bidirectional"))
      (node (ref "Q146") (pin "2") (pinfunction "S_2") (pintype "bidirectional"))
      (node (ref "Q147") (pin "2") (pinfunction "S_2") (pintype "bidirectional"))
      (node (ref "Q148") (pin "2") (pinfunction "S_2") (pintype "bidirectional"))
      (node (ref "Q149") (pin "2") (pinfunction "S_2") (pintype "bidirectional"))
      (node (ref "Q150") (pin "2") (pinfunction "S_2") (pintype "bidirectional"))
      (node (ref "Q151") (pin "2") (pinfunction "S_2") (pintype "bidirectional"))
      (node (ref "Q152") (pin "2") (pinfunction "S_2") (pintype "bidirectional"))
      (node (ref "Q153") (pin "2") (pinfunction "S_2") (pintype "bidirectional"))
      (node (ref "Q154") (pin "2") (pinfunction "S_2") (pintype "bidirectional"))
      (node (ref "Q155") (pin "2") (pinfunction "S_2") (pintype "bidirectional"))
      (node (ref "Q156") (pin "2") (pinfunction "S_2") (pintype "bidirectional"))
      (node (ref "Q157") (pin "2") (pinfunction "S_2") (pintype "bidirectional"))
      (node (ref "Q158") (pin "2") (pinfunction "S_2") (pintype "bidirectional"))
      (node (ref "Q159") (pin "2") (pinfunction "S_2") (pintype "bidirectional"))
      (node (ref "Q160") (pin "2") (pinfunction "S_2") (pintype "bidirectional"))
      (node (ref "Q17") (pin "2") (pinfunction "S_2") (pintype "bidirectional"))
      (node (ref "Q18") (pin "2") (pinfunction "S_2") (pintype "bidirectional"))
      (node (ref "Q193") (pin "2") (pinfunction "S_2") (pintype "bidirectional"))
      (node (ref "Q194") (pin "2") (pinfunction "S_2") (pintype "bidirectional"))
      (node (ref "Q195") (pin "2") (pinfunction "S_2") (pintype "bidirectional"))
      (node (ref "Q196") (pin "2") (pinfunction "S_2") (pintype "bidirectional"))
      (node (ref "Q197") (pin "2") (pinfunction "S_2") (pintype "bidirectional"))
      (node (ref "Q198") (pin "2") (pinfunction "S_2") (pintype "bidirectional"))
      (node (ref "Q199") (pin "2") (pinfunction "S_2") (pintype "bidirectional"))
      (node (ref "Q2") (pin "2") (pinfunction "S_2") (pintype "bidirectional"))
      (node (ref "Q200") (pin "2") (pinfunction "S_2") (pintype "bidirectional"))
      (node (ref "Q201") (pin "2") (pinfunction "S_2") (pintype "bidirectional"))
      (node (ref "Q202") (pin "2") (pinfunction "S_2") (pintype "bidirectional"))
      (node (ref "Q203") (pin "2") (pinfunction "S_2") (pintype "bidirectional"))
      (node (ref "Q204") (pin "2") (pinfunction "S_2") (pintype "bidirectional"))
      (node (ref "Q205") (pin "2") (pinfunction "S_2") (pintype "bidirectional"))
      (node (ref "Q206") (pin "2") (pinfunction "S_2") (pintype "bidirectional"))
      (node (ref "Q207") (pin "2") (pinfunction "S_2") (pintype "bidirectional"))
      (node (ref "Q208") (pin "2") (pinfunction "S_2") (pintype "bidirectional"))
      (node (ref "Q209") (pin "2") (pinfunction "S_2") (pintype "bidirectional"))
      (node (ref "Q21") (pin "2") (pinfunction "S_2") (pintype "bidirectional"))
      (node (ref "Q210") (pin "2") (pinfunction "S_2") (pintype "bidirectional"))
      (node (ref "Q211") (pin "2") (pinfunction "S_2") (pintype "bidirectional"))
      (node (ref "Q212") (pin "2") (pinfunction "S_2") (pintype "bidirectional"))
      (node (ref "Q213") (pin "2") (pinfunction "S_2") (pintype "bidirectional"))
      (node (ref "Q214") (pin "2") (pinfunction "S_2") (pintype "bidirectional"))
      (node (ref "Q215") (pin "2") (pinfunction "S_2") (pintype "bidirectional"))
      (node (ref "Q216") (pin "2") (pinfunction "S_2") (pintype "bidirectional"))
      (node (ref "Q217") (pin "2") (pinfunction "S_2") (pintype "bidirectional"))
      (node (ref "Q218") (pin "2") (pinfunction "S_2") (pintype "bidirectional"))
      (node (ref "Q219") (pin "2") (pinfunction "S_2") (pintype "bidirectional"))
      (node (ref "Q22") (pin "2") (pinfunction "S_2") (pintype "bidirectional"))
      (node (ref "Q220") (pin "2") (pinfunction "S_2") (pintype "bidirectional"))
      (node (ref "Q221") (pin "2") (pinfunction "S_2") (pintype "bidirectional"))
      (node (ref "Q222") (pin "2") (pinfunction "S_2") (pintype "bidirectional"))
      (node (ref "Q223") (pin "2") (pinfunction "S_2") (pintype "bidirectional"))
      (node (ref "Q224") (pin "2") (pinfunction "S_2") (pintype "bidirectional"))
      (node (ref "Q25") (pin "2") (pinfunction "S_2") (pintype "bidirectional"))
      (node (ref "Q257") (pin "2") (pinfunction "S_2") (pintype "bidirectional"))
      (node (ref "Q258") (pin "2") (pinfunction "S_2") (pintype "bidirectional"))
      (node (ref "Q259") (pin "2") (pinfunction "S_2") (pintype "bidirectional"))
      (node (ref "Q26") (pin "2") (pinfunction "S_2") (pintype "bidirectional"))
      (node (ref "Q260") (pin "2") (pinfunction "S_2") (pintype "bidirectional"))
      (node (ref "Q261") (pin "2") (pinfunction "S_2") (pintype "bidirectional"))
      (node (ref "Q262") (pin "2") (pinfunction "S_2") (pintype "bidirectional"))
      (node (ref "Q263") (pin "2") (pinfunction "S_2") (pintype "bidirectional"))
      (node (ref "Q264") (pin "2") (pinfunction "S_2") (pintype "bidirectional"))
      (node (ref "Q265") (pin "2") (pinfunction "S_2") (pintype "bidirectional"))
      (node (ref "Q266") (pin "2") (pinfunction "S_2") (pintype "bidirectional"))
      (node (ref "Q267") (pin "2") (pinfunction "S_2") (pintype "bidirectional"))
      (node (ref "Q268") (pin "2") (pinfunction "S_2") (pintype "bidirectional"))
      (node (ref "Q269") (pin "2") (pinfunction "S_2") (pintype "bidirectional"))
      (node (ref "Q270") (pin "2") (pinfunction "S_2") (pintype "bidirectional"))
      (node (ref "Q271") (pin "2") (pinfunction "S_2") (pintype "bidirectional"))
      (node (ref "Q272") (pin "2") (pinfunction "S_2") (pintype "bidirectional"))
      (node (ref "Q273") (pin "2") (pinfunction "S_2") (pintype "bidirectional"))
      (node (ref "Q274") (pin "2") (pinfunction "S_2") (pintype "bidirectional"))
      (node (ref "Q275") (pin "2") (pinfunction "S_2") (pintype "bidirectional"))
      (node (ref "Q276") (pin "2") (pinfunction "S_2") (pintype "bidirectional"))
      (node (ref "Q277") (pin "2") (pinfunction "S_2") (pintype "bidirectional"))
      (node (ref "Q278") (pin "2") (pinfunction "S_2") (pintype "bidirectional"))
      (node (ref "Q279") (pin "2") (pinfunction "S_2") (pintype "bidirectional"))
      (node (ref "Q280") (pin "2") (pinfunction "S_2") (pintype "bidirectional"))
      (node (ref "Q281") (pin "2") (pinfunction "S_2") (pintype "bidirectional"))
      (node (ref "Q282") (pin "2") (pinfunction "S_2") (pintype "bidirectional"))
      (node (ref "Q283") (pin "2") (pinfunction "S_2") (pintype "bidirectional"))
      (node (ref "Q284") (pin "2") (pinfunction "S_2") (pintype "bidirectional"))
      (node (ref "Q285") (pin "2") (pinfunction "S_2") (pintype "bidirectional"))
      (node (ref "Q286") (pin "2") (pinfunction "S_2") (pintype "bidirectional"))
      (node (ref "Q287") (pin "2") (pinfunction "S_2") (pintype "bidirectional"))
      (node (ref "Q288") (pin "2") (pinfunction "S_2") (pintype "bidirectional"))
      (node (ref "Q29") (pin "2") (pinfunction "S_2") (pintype "bidirectional"))
      (node (ref "Q30") (pin "2") (pinfunction "S_2") (pintype "bidirectional"))
      (node (ref "Q321") (pin "2") (pinfunction "S_2") (pintype "bidirectional"))
      (node (ref "Q322") (pin "2") (pinfunction "S_2") (pintype "bidirectional"))
      (node (ref "Q323") (pin "2") (pinfunction "S_2") (pintype "bidirectional"))
      (node (ref "Q324") (pin "2") (pinfunction "S_2") (pintype "bidirectional"))
      (node (ref "Q325") (pin "2") (pinfunction "S_2") (pintype "bidirectional"))
      (node (ref "Q326") (pin "2") (pinfunction "S_2") (pintype "bidirectional"))
      (node (ref "Q327") (pin "2") (pinfunction "S_2") (pintype "bidirectional"))
      (node (ref "Q328") (pin "2") (pinfunction "S_2") (pintype "bidirectional"))
      (node (ref "Q329") (pin "2") (pinfunction "S_2") (pintype "bidirectional"))
      (node (ref "Q33") (pin "2") (pinfunction "S_2") (pintype "bidirectional"))
      (node (ref "Q330") (pin "2") (pinfunction "S_2") (pintype "bidirectional"))
      (node (ref "Q331") (pin "2") (pinfunction "S_2") (pintype "bidirectional"))
      (node (ref "Q332") (pin "2") (pinfunction "S_2") (pintype "bidirectional"))
      (node (ref "Q333") (pin "2") (pinfunction "S_2") (pintype "bidirectional"))
      (node (ref "Q334") (pin "2") (pinfunction "S_2") (pintype "bidirectional"))
      (node (ref "Q335") (pin "2") (pinfunction "S_2") (pintype "bidirectional"))
      (node (ref "Q336") (pin "2") (pinfunction "S_2") (pintype "bidirectional"))
      (node (ref "Q337") (pin "2") (pinfunction "S_2") (pintype "bidirectional"))
      (node (ref "Q338") (pin "2") (pinfunction "S_2") (pintype "bidirectional"))
      (node (ref "Q339") (pin "2") (pinfunction "S_2") (pintype "bidirectional"))
      (node (ref "Q34") (pin "2") (pinfunction "S_2") (pintype "bidirectional"))
      (node (ref "Q340") (pin "2") (pinfunction "S_2") (pintype "bidirectional"))
      (node (ref "Q341") (pin "2") (pinfunction "S_2") (pintype "bidirectional"))
      (node (ref "Q342") (pin "2") (pinfunction "S_2") (pintype "bidirectional"))
      (node (ref "Q343") (pin "2") (pinfunction "S_2") (pintype "bidirectional"))
      (node (ref "Q344") (pin "2") (pinfunction "S_2") (pintype "bidirectional"))
      (node (ref "Q345") (pin "2") (pinfunction "S_2") (pintype "bidirectional"))
      (node (ref "Q346") (pin "2") (pinfunction "S_2") (pintype "bidirectional"))
      (node (ref "Q347") (pin "2") (pinfunction "S_2") (pintype "bidirectional"))
      (node (ref "Q348") (pin "2") (pinfunction "S_2") (pintype "bidirectional"))
      (node (ref "Q349") (pin "2") (pinfunction "S_2") (pintype "bidirectional"))
      (node (ref "Q350") (pin "2") (pinfunction "S_2") (pintype "bidirectional"))
      (node (ref "Q351") (pin "2") (pinfunction "S_2") (pintype "bidirectional"))
      (node (ref "Q352") (pin "2") (pinfunction "S_2") (pintype "bidirectional"))
      (node (ref "Q37") (pin "2") (pinfunction "S_2") (pintype "bidirectional"))
      (node (ref "Q38") (pin "2") (pinfunction "S_2") (pintype "bidirectional"))
      (node (ref "Q41") (pin "2") (pinfunction "S_2") (pintype "bidirectional"))
      (node (ref "Q42") (pin "2") (pinfunction "S_2") (pintype "bidirectional"))
      (node (ref "Q45") (pin "2") (pinfunction "S_2") (pintype "bidirectional"))
      (node (ref "Q46") (pin "2") (pinfunction "S_2") (pintype "bidirectional"))
      (node (ref "Q49") (pin "2") (pinfunction "S_2") (pintype "bidirectional"))
      (node (ref "Q5") (pin "2") (pinfunction "S_2") (pintype "bidirectional"))
      (node (ref "Q50") (pin "2") (pinfunction "S_2") (pintype "bidirectional"))
      (node (ref "Q53") (pin "2") (pinfunction "S_2") (pintype "bidirectional"))
      (node (ref "Q54") (pin "2") (pinfunction "S_2") (pintype "bidirectional"))
      (node (ref "Q57") (pin "2") (pinfunction "S_2") (pintype "bidirectional"))
      (node (ref "Q58") (pin "2") (pinfunction "S_2") (pintype "bidirectional"))
      (node (ref "Q6") (pin "2") (pinfunction "S_2") (pintype "bidirectional"))
      (node (ref "Q61") (pin "2") (pinfunction "S_2") (pintype "bidirectional"))
      (node (ref "Q62") (pin "2") (pinfunction "S_2") (pintype "bidirectional"))
      (node (ref "Q65") (pin "2") (pinfunction "S_2") (pintype "bidirectional"))
      (node (ref "Q66") (pin "2") (pinfunction "S_2") (pintype "bidirectional"))
      (node (ref "Q67") (pin "2") (pinfunction "S_2") (pintype "bidirectional"))
      (node (ref "Q68") (pin "2") (pinfunction "S_2") (pintype "bidirectional"))
      (node (ref "Q69") (pin "2") (pinfunction "S_2") (pintype "bidirectional"))
      (node (ref "Q70") (pin "2") (pinfunction "S_2") (pintype "bidirectional"))
      (node (ref "Q71") (pin "2") (pinfunction "S_2") (pintype "bidirectional"))
      (node (ref "Q72") (pin "2") (pinfunction "S_2") (pintype "bidirectional"))
      (node (ref "Q73") (pin "2") (pinfunction "S_2") (pintype "bidirectional"))
      (node (ref "Q74") (pin "2") (pinfunction "S_2") (pintype "bidirectional"))
      (node (ref "Q75") (pin "2") (pinfunction "S_2") (pintype "bidirectional"))
      (node (ref "Q76") (pin "2") (pinfunction "S_2") (pintype "bidirectional"))
      (node (ref "Q77") (pin "2") (pinfunction "S_2") (pintype "bidirectional"))
      (node (ref "Q78") (pin "2") (pinfunction "S_2") (pintype "bidirectional"))
      (node (ref "Q79") (pin "2") (pinfunction "S_2") (pintype "bidirectional"))
      (node (ref "Q80") (pin "2") (pinfunction "S_2") (pintype "bidirectional"))
      (node (ref "Q81") (pin "2") (pinfunction "S_2") (pintype "bidirectional"))
      (node (ref "Q82") (pin "2") (pinfunction "S_2") (pintype "bidirectional"))
      (node (ref "Q83") (pin "2") (pinfunction "S_2") (pintype "bidirectional"))
      (node (ref "Q84") (pin "2") (pinfunction "S_2") (pintype "bidirectional"))
      (node (ref "Q85") (pin "2") (pinfunction "S_2") (pintype "bidirectional"))
      (node (ref "Q86") (pin "2") (pinfunction "S_2") (pintype "bidirectional"))
      (node (ref "Q87") (pin "2") (pinfunction "S_2") (pintype "bidirectional"))
      (node (ref "Q88") (pin "2") (pinfunction "S_2") (pintype "bidirectional"))
      (node (ref "Q89") (pin "2") (pinfunction "S_2") (pintype "bidirectional"))
      (node (ref "Q9") (pin "2") (pinfunction "S_2") (pintype "bidirectional"))
      (node (ref "Q90") (pin "2") (pinfunction "S_2") (pintype "bidirectional"))
      (node (ref "Q91") (pin "2") (pinfunction "S_2") (pintype "bidirectional"))
      (node (ref "Q92") (pin "2") (pinfunction "S_2") (pintype "bidirectional"))
      (node (ref "Q93") (pin "2") (pinfunction "S_2") (pintype "bidirectional"))
      (node (ref "Q94") (pin "2") (pinfunction "S_2") (pintype "bidirectional"))
      (node (ref "Q95") (pin "2") (pinfunction "S_2") (pintype "bidirectional"))
      (node (ref "Q96") (pin "2") (pinfunction "S_2") (pintype "bidirectional"))
    )
    (net (code "5") (name "P1") (class "Default")
      (node (ref "JP2") (pin "1") (pinfunction "1_1") (pintype "passive"))
    )
    (net (code "6") (name "P2") (class "Default")
      (node (ref "JP2") (pin "2") (pinfunction "2_2") (pintype "passive"))
    )
    (net (code "7") (name "P3") (class "Default")
      (node (ref "JP2") (pin "3") (pinfunction "3_3") (pintype "passive"))
    )
    (net (code "8") (name "P4") (class "Default")
      (node (ref "JP2") (pin "4") (pinfunction "4_4") (pintype "passive"))
    )
    (net (code "9") (name "P5") (class "Default")
      (node (ref "JP2") (pin "5") (pinfunction "5_5") (pintype "passive"))
    )
    (net (code "10") (name "P6") (class "Default")
      (node (ref "JP2") (pin "6") (pinfunction "6_6") (pintype "passive"))
    )
    (net (code "11") (name "P7") (class "Default")
      (node (ref "JP2") (pin "7") (pinfunction "7_7") (pintype "passive"))
    )
    (net (code "12") (name "P8") (class "Default")
      (node (ref "JP2") (pin "8") (pinfunction "8_8") (pintype "passive"))
    )
    (net (code "13") (name "P9") (class "Default")
      (node (ref "JP2") (pin "9") (pinfunction "9_9") (pintype "passive"))
    )
    (net (code "14") (name "P10") (class "Default")
      (node (ref "JP2") (pin "10") (pinfunction "10_10") (pintype "passive"))
    )
    (net (code "15") (name "P11") (class "Default")
      (node (ref "JP2") (pin "11") (pinfunction "11_11") (pintype "passive"))
    )
    (net (code "16") (name "P12") (class "Default")
      (node (ref "JP2") (pin "12") (pinfunction "12_12") (pintype "passive"))
    )
    (net (code "17") (name "P13") (class "Default")
      (node (ref "JP2") (pin "13") (pinfunction "13_13") (pintype "passive"))
    )
    (net (code "18") (name "P14") (class "Default")
      (node (ref "JP2") (pin "14") (pinfunction "14_14") (pintype "passive"))
    )
    (net (code "19") (name "P15") (class "Default")
      (node (ref "JP2") (pin "15") (pinfunction "15_15") (pintype "passive"))
    )
    (net (code "20") (name "P16") (class "Default")
      (node (ref "JP2") (pin "16") (pinfunction "16_16") (pintype "passive"))
    )
    (net (code "21") (name "P17") (class "Default")
      (node (ref "JP2") (pin "17") (pinfunction "17_17") (pintype "passive"))
    )
    (net (code "22") (name "P18") (class "Default")
      (node (ref "JP2") (pin "18") (pinfunction "18_18") (pintype "passive"))
    )
    (net (code "23") (name "P19") (class "Default")
      (node (ref "JP2") (pin "19") (pinfunction "19_19") (pintype "passive"))
    )
    (net (code "24") (name "P20") (class "Default")
      (node (ref "JP2") (pin "20") (pinfunction "20_20") (pintype "passive"))
    )
    (net (code "25") (name "P21") (class "Default")
      (node (ref "JP2") (pin "21") (pinfunction "21_21") (pintype "passive"))
    )
    (net (code "26") (name "P22") (class "Default")
      (node (ref "JP2") (pin "22") (pinfunction "22_22") (pintype "passive"))
    )
    (net (code "27") (name "P23") (class "Default")
      (node (ref "JP2") (pin "23") (pinfunction "23_23") (pintype "passive"))
    )
    (net (code "28") (name "P24") (class "Default")
      (node (ref "JP2") (pin "24") (pinfunction "24_24") (pintype "passive"))
    )
    (net (code "29") (name "P25") (class "Default")
      (node (ref "JP2") (pin "25") (pinfunction "25_25") (pintype "passive"))
    )
    (net (code "30") (name "P26") (class "Default")
      (node (ref "JP2") (pin "26") (pinfunction "26_26") (pintype "passive"))
    )
    (net (code "31") (name "P27") (class "Default")
      (node (ref "JP2") (pin "27") (pinfunction "27_27") (pintype "passive"))
    )
    (net (code "32") (name "P28") (class "Default")
      (node (ref "JP2") (pin "28") (pinfunction "28_28") (pintype "passive"))
    )
    (net (code "33") (name "VCC") (class "Default")
      (node (ref "C10") (pin "1") (pinfunction "1_1") (pintype "passive"))
      (node (ref "C12") (pin "1") (pinfunction "1_1") (pintype "passive"))
      (node (ref "C14") (pin "1") (pinfunction "1_1") (pintype "passive"))
      (node (ref "C16") (pin "1") (pinfunction "1_1") (pintype "passive"))
      (node (ref "C2") (pin "1") (pinfunction "1_1") (pintype "passive"))
      (node (ref "C4") (pin "1") (pinfunction "1_1") (pintype "passive"))
      (node (ref "C6") (pin "1") (pinfunction "1_1") (pintype "passive"))
      (node (ref "C8") (pin "1") (pinfunction "1_1") (pintype "passive"))
      (node (ref "JP2") (pin "29") (pinfunction "29_29") (pintype "passive"))
      (node (ref "R1") (pin "1") (pinfunction "1_1") (pintype "passive"))
      (node (ref "R100") (pin "1") (pinfunction "1_1") (pintype "passive"))
      (node (ref "R101") (pin "1") (pinfunction "1_1") (pintype "passive"))
      (node (ref "R102") (pin "1") (pinfunction "1_1") (pintype "passive"))
      (node (ref "R103") (pin "1") (pinfunction "1_1") (pintype "passive"))
      (node (ref "R104") (pin "1") (pinfunction "1_1") (pintype "passive"))
      (node (ref "R105") (pin "1") (pinfunction "1_1") (pintype "passive"))
      (node (ref "R106") (pin "1") (pinfunction "1_1") (pintype "passive"))
      (node (ref "R107") (pin "1") (pinfunction "1_1") (pintype "passive"))
      (node (ref "R108") (pin "1") (pinfunction "1_1") (pintype "passive"))
      (node (ref "R109") (pin "1") (pinfunction "1_1") (pintype "passive"))
      (node (ref "R11") (pin "1") (pinfunction "1_1") (pintype "passive"))
      (node (ref "R110") (pin "1") (pinfunction "1_1") (pintype "passive"))
      (node (ref "R111") (pin "1") (pinfunction "1_1") (pintype "passive"))
      (node (ref "R112") (pin "1") (pinfunction "1_1") (pintype "passive"))
      (node (ref "R129") (pin "1") (pinfunction "1_1") (pintype "passive"))
      (node (ref "R13") (pin "1") (pinfunction "1_1") (pintype "passive"))
      (node (ref "R130") (pin "1") (pinfunction "1_1") (pintype "passive"))
      (node (ref "R131") (pin "1") (pinfunction "1_1") (pintype "passive"))
      (node (ref "R132") (pin "1") (pinfunction "1_1") (pintype "passive"))
      (node (ref "R133") (pin "1") (pinfunction "1_1") (pintype "passive"))
      (node (ref "R134") (pin "1") (pinfunction "1_1") (pintype "passive"))
      (node (ref "R135") (pin "1") (pinfunction "1_1") (pintype "passive"))
      (node (ref "R136") (pin "1") (pinfunction "1_1") (pintype "passive"))
      (node (ref "R137") (pin "1") (pinfunction "1_1") (pintype "passive"))
      (node (ref "R138") (pin "1") (pinfunction "1_1") (pintype "passive"))
      (node (ref "R139") (pin "1") (pinfunction "1_1") (pintype "passive"))
      (node (ref "R140") (pin "1") (pinfunction "1_1") (pintype "passive"))
      (node (ref "R141") (pin "1") (pinfunction "1_1") (pintype "passive"))
      (node (ref "R142") (pin "1") (pinfunction "1_1") (pintype "passive"))
      (node (ref "R143") (pin "1") (pinfunction "1_1") (pintype "passive"))
      (node (ref "R144") (pin "1") (pinfunction "1_1") (pintype "passive"))
      (node (ref "R15") (pin "1") (pinfunction "1_1") (pintype "passive"))
      (node (ref "R161") (pin "1") (pinfunction "1_1") (pintype "passive"))
      (node (ref "R162") (pin "1") (pinfunction "1_1") (pintype "passive"))
      (node (ref "R163") (pin "1") (pinfunction "1_1") (pintype "passive"))
      (node (ref "R164") (pin "1") (pinfunction "1_1") (pintype "passive"))
      (node (ref "R165") (pin "1") (pinfunction "1_1") (pintype "passive"))
      (node (ref "R166") (pin "1") (pinfunction "1_1") (pintype "passive"))
      (node (ref "R167") (pin "1") (pinfunction "1_1") (pintype "passive"))
      (node (ref "R168") (pin "1") (pinfunction "1_1") (pintype "passive"))
      (node (ref "R169") (pin "1") (pinfunction "1_1") (pintype "passive"))
      (node (ref "R17") (pin "1") (pinfunction "1_1") (pintype "passive"))
      (node (ref "R170") (pin "1") (pinfunction "1_1") (pintype "passive"))
      (node (ref "R171") (pin "1") (pinfunction "1_1") (pintype "passive"))
      (node (ref "R172") (pin "1") (pinfunction "1_1") (pintype "passive"))
      (node (ref "R173") (pin "1") (pinfunction "1_1") (pintype "passive"))
      (node (ref "R174") (pin "1") (pinfunction "1_1") (pintype "passive"))
      (node (ref "R175") (pin "1") (pinfunction "1_1") (pintype "passive"))
      (node (ref "R176") (pin "1") (pinfunction "1_1") (pintype "passive"))
      (node (ref "R19") (pin "1") (pinfunction "1_1") (pintype "passive"))
      (node (ref "R21") (pin "1") (pinfunction "1_1") (pintype "passive"))
      (node (ref "R23") (pin "1") (pinfunction "1_1") (pintype "passive"))
      (node (ref "R25") (pin "1") (pinfunction "1_1") (pintype "passive"))
      (node (ref "R27") (pin "1") (pinfunction "1_1") (pintype "passive"))
      (node (ref "R29") (pin "1") (pinfunction "1_1") (pintype "passive"))
      (node (ref "R3") (pin "1") (pinfunction "1_1") (pintype "passive"))
      (node (ref "R31") (pin "1") (pinfunction "1_1") (pintype "passive"))
      (node (ref "R33") (pin "1") (pinfunction "1_1") (pintype "passive"))
      (node (ref "R34") (pin "1") (pinfunction "1_1") (pintype "passive"))
      (node (ref "R35") (pin "1") (pinfunction "1_1") (pintype "passive"))
      (node (ref "R36") (pin "1") (pinfunction "1_1") (pintype "passive"))
      (node (ref "R37") (pin "1") (pinfunction "1_1") (pintype "passive"))
      (node (ref "R38") (pin "1") (pinfunction "1_1") (pintype "passive"))
      (node (ref "R39") (pin "1") (pinfunction "1_1") (pintype "passive"))
      (node (ref "R40") (pin "1") (pinfunction "1_1") (pintype "passive"))
      (node (ref "R41") (pin "1") (pinfunction "1_1") (pintype "passive"))
      (node (ref "R42") (pin "1") (pinfunction "1_1") (pintype "passive"))
      (node (ref "R43") (pin "1") (pinfunction "1_1") (pintype "passive"))
      (node (ref "R44") (pin "1") (pinfunction "1_1") (pintype "passive"))
      (node (ref "R45") (pin "1") (pinfunction "1_1") (pintype "passive"))
      (node (ref "R46") (pin "1") (pinfunction "1_1") (pintype "passive"))
      (node (ref "R47") (pin "1") (pinfunction "1_1") (pintype "passive"))
      (node (ref "R48") (pin "1") (pinfunction "1_1") (pintype "passive"))
      (node (ref "R5") (pin "1") (pinfunction "1_1") (pintype "passive"))
      (node (ref "R65") (pin "1") (pinfunction "1_1") (pintype "passive"))
      (node (ref "R66") (pin "1") (pinfunction "1_1") (pintype "passive"))
      (node (ref "R67") (pin "1") (pinfunction "1_1") (pintype "passive"))
      (node (ref "R68") (pin "1") (pinfunction "1_1") (pintype "passive"))
      (node (ref "R69") (pin "1") (pinfunction "1_1") (pintype "passive"))
      (node (ref "R7") (pin "1") (pinfunction "1_1") (pintype "passive"))
      (node (ref "R70") (pin "1") (pinfunction "1_1") (pintype "passive"))
      (node (ref "R71") (pin "1") (pinfunction "1_1") (pintype "passive"))
      (node (ref "R72") (pin "1") (pinfunction "1_1") (pintype "passive"))
      (node (ref "R73") (pin "1") (pinfunction "1_1") (pintype "passive"))
      (node (ref "R74") (pin "1") (pinfunction "1_1") (pintype "passive"))
      (node (ref "R75") (pin "1") (pinfunction "1_1") (pintype "passive"))
      (node (ref "R76") (pin "1") (pinfunction "1_1") (pintype "passive"))
      (node (ref "R77") (pin "1") (pinfunction "1_1") (pintype "passive"))
      (node (ref "R78") (pin "1") (pinfunction "1_1") (pintype "passive"))
      (node (ref "R79") (pin "1") (pinfunction "1_1") (pintype "passive"))
      (node (ref "R80") (pin "1") (pinfunction "1_1") (pintype "passive"))
      (node (ref "R9") (pin "1") (pinfunction "1_1") (pintype "passive"))
      (node (ref "R97") (pin "1") (pinfunction "1_1") (pintype "passive"))
      (node (ref "R98") (pin "1") (pinfunction "1_1") (pintype "passive"))
      (node (ref "R99") (pin "1") (pinfunction "1_1") (pintype "passive"))
    )
  )
)
